# NHK2016mother.net
KiCad netlist of a schematic drawn in EAGLE
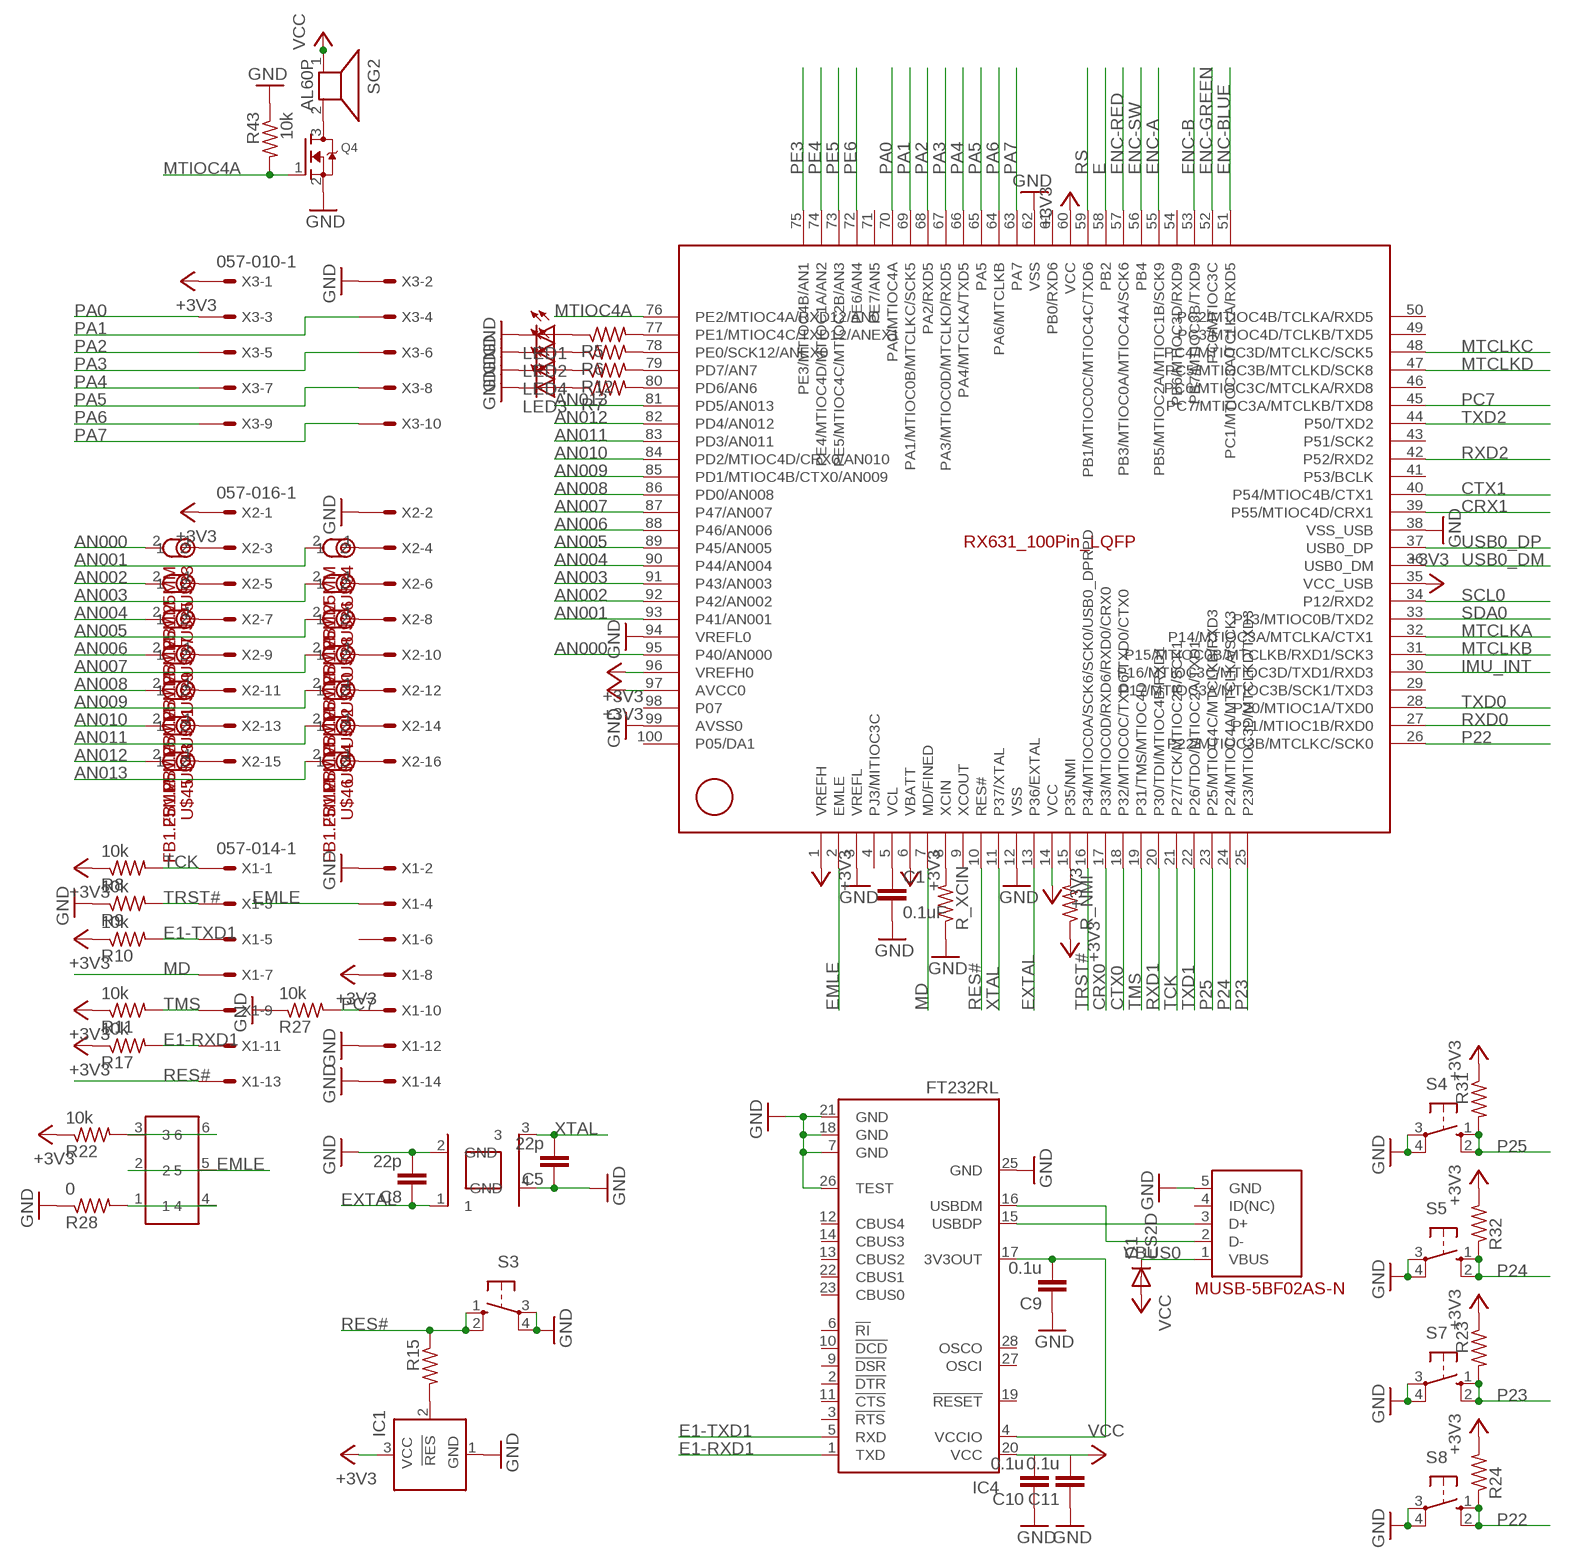
[diagram p0: schematic, sheet 1, part 1 of 2]
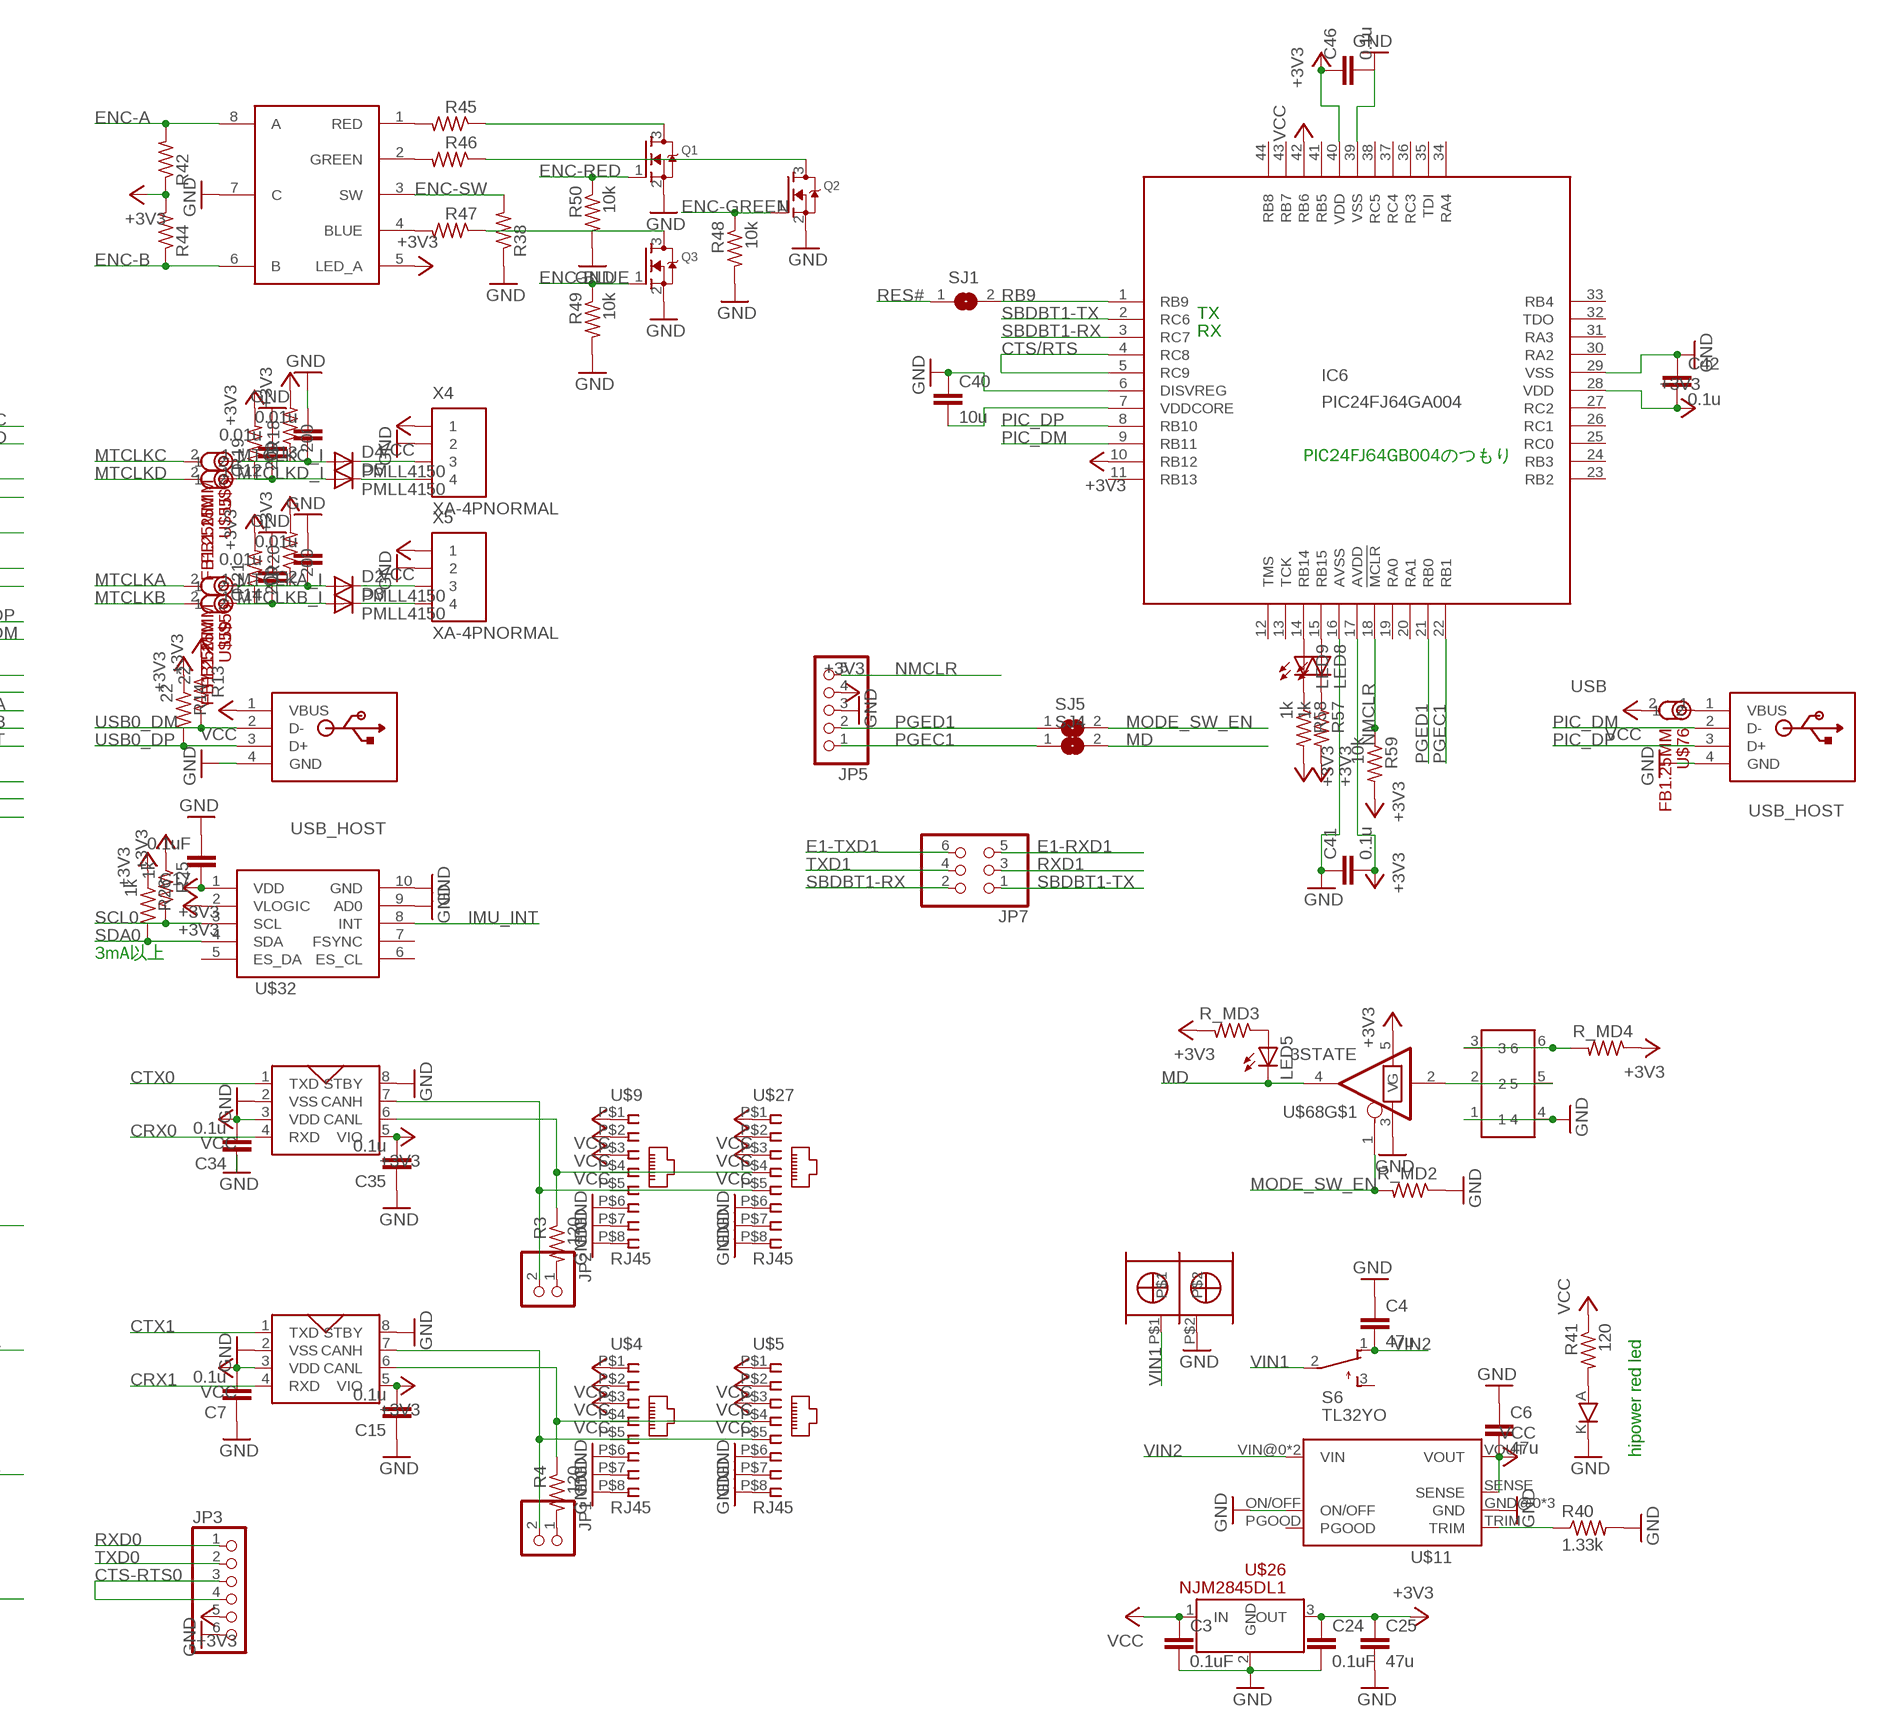
[diagram p1: schematic, sheet 1, part 2 of 2]

(export (version "E")
  (design (tool "Eeschema 10.0.6"))
  (components
    (comp (ref "C1")
      (value "0.1uF")
      (footprint "eagle-import:C0603K")
      (libsource (lib "eagle-import") (part "C-EUC0603K"))
    )
    (comp (ref "C2")
      (value "0.01u")
      (footprint "eagle-import:C0402")
      (libsource (lib "eagle-import") (part "C-EUC0402"))
    )
    (comp (ref "C3")
      (value "0.1uF")
      (footprint "eagle-import:C0603K")
      (libsource (lib "eagle-import") (part "C-EUC0603K"))
    )
    (comp (ref "C4")
      (value "47u")
      (footprint "eagle-import:C3225")
      (libsource (lib "eagle-import") (part "C-EUC3225"))
    )
    (comp (ref "C5")
      (value "22p")
      (footprint "eagle-import:C0603K")
      (libsource (lib "eagle-import") (part "C-EUC0603K"))
    )
    (comp (ref "C6")
      (value "47u")
      (footprint "eagle-import:C3225")
      (libsource (lib "eagle-import") (part "C-EUC3225"))
    )
    (comp (ref "C7")
      (value "0.1u")
      (footprint "eagle-import:C0402")
      (libsource (lib "eagle-import") (part "C-EUC0402"))
    )
    (comp (ref "C8")
      (value "22p")
      (footprint "eagle-import:C0603K")
      (libsource (lib "eagle-import") (part "C-EUC0603K"))
    )
    (comp (ref "C9")
      (value "0.1u")
      (footprint "eagle-import:C0402")
      (libsource (lib "eagle-import") (part "C-EUC0402"))
    )
    (comp (ref "C10")
      (value "0.1u")
      (footprint "eagle-import:C0402")
      (libsource (lib "eagle-import") (part "C-EUC0402"))
    )
    (comp (ref "C11")
      (value "0.1u")
      (footprint "eagle-import:C0402")
      (libsource (lib "eagle-import") (part "C-EUC0402"))
    )
    (comp (ref "C12")
      (value "0.01u")
      (footprint "eagle-import:C0402")
      (libsource (lib "eagle-import") (part "C-EUC0402"))
    )
    (comp (ref "C13")
      (value "0.01u")
      (footprint "eagle-import:C0402")
      (libsource (lib "eagle-import") (part "C-EUC0402"))
    )
    (comp (ref "C14")
      (value "0.01u")
      (footprint "eagle-import:C0402")
      (libsource (lib "eagle-import") (part "C-EUC0402"))
    )
    (comp (ref "C15")
      (value "0.1u")
      (footprint "eagle-import:C0402")
      (libsource (lib "eagle-import") (part "C-EUC0402"))
    )
    (comp (ref "C17")
      (value "0.1uF")
      (footprint "eagle-import:C0603K")
      (libsource (lib "eagle-import") (part "C-EUC0603K"))
    )
    (comp (ref "C24")
      (value "0.1uF")
      (footprint "eagle-import:C0603K")
      (libsource (lib "eagle-import") (part "C-EUC0603K"))
    )
    (comp (ref "C25")
      (value "47u")
      (footprint "eagle-import:C3225")
      (libsource (lib "eagle-import") (part "C-EUC3225"))
    )
    (comp (ref "C34")
      (value "0.1u")
      (footprint "eagle-import:C0402")
      (libsource (lib "eagle-import") (part "C-EUC0402"))
    )
    (comp (ref "C35")
      (value "0.1u")
      (footprint "eagle-import:C0402")
      (libsource (lib "eagle-import") (part "C-EUC0402"))
    )
    (comp (ref "C40")
      (value "10u")
      (footprint "eagle-import:C0603K")
      (libsource (lib "eagle-import") (part "C-EUC0603K"))
    )
    (comp (ref "C41")
      (value "0.1u")
      (footprint "eagle-import:C0603K")
      (libsource (lib "eagle-import") (part "C-EUC0603K"))
    )
    (comp (ref "C42")
      (value "0.1u")
      (footprint "eagle-import:C0603K")
      (libsource (lib "eagle-import") (part "C-EUC0603K"))
    )
    (comp (ref "C46")
      (value "0.1u")
      (footprint "eagle-import:C0603K")
      (libsource (lib "eagle-import") (part "C-EUC0603K"))
    )
    (comp (ref "D1")
      (value "ES2D")
      (footprint "eagle-import:SMB")
      (libsource (lib "eagle-import") (part "ES2D"))
    )
    (comp (ref "D2")
      (value "PMLL4150")
      (footprint "eagle-import:SOD80C")
      (libsource (lib "eagle-import") (part "PMLL4150"))
    )
    (comp (ref "D3")
      (value "PMLL4150")
      (footprint "eagle-import:SOD80C")
      (libsource (lib "eagle-import") (part "PMLL4150"))
    )
    (comp (ref "D4")
      (value "PMLL4150")
      (footprint "eagle-import:SOD80C")
      (libsource (lib "eagle-import") (part "PMLL4150"))
    )
    (comp (ref "D5")
      (value "PMLL4150")
      (footprint "eagle-import:SOD80C")
      (libsource (lib "eagle-import") (part "PMLL4150"))
    )
    (comp (ref "IC1")
      (value "TCM809")
      (footprint "eagle-import:SOT23B-3")
      (fields (field (name "MF") "MICROCHIP") (field (name "MPN") "TCM809MENB713"))
      (libsource (lib "eagle-import") (part "TCM809"))
    )
    (comp (ref "IC4")
      (value "FT232RL")
      (footprint "eagle-import:SSOP28")
      (libsource (lib "eagle-import") (part "FT232RL"))
    )
    (comp (ref "IC6")
      (value "PIC24FJ64GA004")
      (footprint "eagle-import:TQFP44")
      (fields (field (name "MPN") "PIC24FJ64GA004-E/PT"))
      (libsource (lib "eagle-import") (part "PIC24FJ64GA004"))
    )
    (comp (ref "JP1")
      (value "PINHD-1X2")
      (footprint "eagle-import:1X02")
      (libsource (lib "eagle-import") (part "PINHD-1X2"))
    )
    (comp (ref "JP2")
      (value "PINHD-1X2")
      (footprint "eagle-import:1X02")
      (libsource (lib "eagle-import") (part "PINHD-1X2"))
    )
    (comp (ref "JP3")
      (value "PINHD-1X6")
      (footprint "eagle-import:1X06")
      (libsource (lib "eagle-import") (part "PINHD-1X6"))
    )
    (comp (ref "JP5")
      (value "PINHD-1X5")
      (footprint "eagle-import:1X05")
      (libsource (lib "eagle-import") (part "PINHD-1X5"))
    )
    (comp (ref "JP7")
      (value "PINHD-2X3")
      (footprint "eagle-import:2X03")
      (libsource (lib "eagle-import") (part "PINHD-2X3"))
    )
    (comp (ref "LED1")
      (value "LEDSML0805")
      (footprint "eagle-import:SML0805")
      (libsource (lib "eagle-import") (part "LEDSML0805"))
    )
    (comp (ref "LED2")
      (value "LEDSML0805")
      (footprint "eagle-import:SML0805")
      (libsource (lib "eagle-import") (part "LEDSML0805"))
    )
    (comp (ref "LED3")
      (value "LEDSML0805")
      (footprint "eagle-import:SML0805")
      (libsource (lib "eagle-import") (part "LEDSML0805"))
    )
    (comp (ref "LED4")
      (value "LEDSML0805")
      (footprint "eagle-import:SML0805")
      (libsource (lib "eagle-import") (part "LEDSML0805"))
    )
    (comp (ref "LED5")
      (value "LEDSML0805")
      (footprint "eagle-import:SML0805")
      (libsource (lib "eagle-import") (part "LEDSML0805"))
    )
    (comp (ref "LED8")
      (value "LEDSML0805")
      (footprint "eagle-import:SML0805")
      (libsource (lib "eagle-import") (part "LEDSML0805"))
    )
    (comp (ref "LED9")
      (value "LEDSML0805")
      (footprint "eagle-import:SML0805")
      (libsource (lib "eagle-import") (part "LEDSML0805"))
    )
    (comp (ref "Q1")
      (value "MOSFET-NREFLOW")
      (footprint "eagle-import:SOT23")
      (libsource (lib "eagle-import") (part "MOSFET-NREFLOW"))
    )
    (comp (ref "Q2")
      (value "MOSFET-NREFLOW")
      (footprint "eagle-import:SOT23")
      (libsource (lib "eagle-import") (part "MOSFET-NREFLOW"))
    )
    (comp (ref "Q3")
      (value "MOSFET-NREFLOW")
      (footprint "eagle-import:SOT23")
      (libsource (lib "eagle-import") (part "MOSFET-NREFLOW"))
    )
    (comp (ref "Q4")
      (value "MOSFET-NREFLOW")
      (footprint "eagle-import:SOT23")
      (libsource (lib "eagle-import") (part "MOSFET-NREFLOW"))
    )
    (comp (ref "R3")
      (value "120")
      (footprint "eagle-import:MINI_MELF-0102W")
      (libsource (lib "eagle-import") (part "R-US_MELF0102W"))
    )
    (comp (ref "R4")
      (value "120")
      (footprint "eagle-import:MINI_MELF-0102W")
      (libsource (lib "eagle-import") (part "R-US_MELF0102W"))
    )
    (comp (ref "R5")
      (value "R-US_MELF0102W")
      (footprint "eagle-import:MINI_MELF-0102W")
      (libsource (lib "eagle-import") (part "R-US_MELF0102W"))
    )
    (comp (ref "R6")
      (value "R-US_MELF0102W")
      (footprint "eagle-import:MINI_MELF-0102W")
      (libsource (lib "eagle-import") (part "R-US_MELF0102W"))
    )
    (comp (ref "R7")
      (value "R-US_MELF0102W")
      (footprint "eagle-import:MINI_MELF-0102W")
      (libsource (lib "eagle-import") (part "R-US_MELF0102W"))
    )
    (comp (ref "R8")
      (value "10k")
      (footprint "eagle-import:MINI_MELF-0102W")
      (libsource (lib "eagle-import") (part "R-US_MELF0102W"))
    )
    (comp (ref "R9")
      (value "10k")
      (footprint "eagle-import:MINI_MELF-0102W")
      (libsource (lib "eagle-import") (part "R-US_MELF0102W"))
    )
    (comp (ref "R10")
      (value "10k")
      (footprint "eagle-import:MINI_MELF-0102W")
      (libsource (lib "eagle-import") (part "R-US_MELF0102W"))
    )
    (comp (ref "R11")
      (value "10k")
      (footprint "eagle-import:MINI_MELF-0102W")
      (libsource (lib "eagle-import") (part "R-US_MELF0102W"))
    )
    (comp (ref "R12")
      (value "R-US_MELF0102W")
      (footprint "eagle-import:MINI_MELF-0102W")
      (libsource (lib "eagle-import") (part "R-US_MELF0102W"))
    )
    (comp (ref "R13")
      (value "22")
      (footprint "eagle-import:MINI_MELF-0102W")
      (libsource (lib "eagle-import") (part "R-US_MELF0102W"))
    )
    (comp (ref "R14")
      (value "22")
      (footprint "eagle-import:MINI_MELF-0102W")
      (libsource (lib "eagle-import") (part "R-US_MELF0102W"))
    )
    (comp (ref "R15")
      (value "R-US_MELF0102W")
      (footprint "eagle-import:MINI_MELF-0102W")
      (libsource (lib "eagle-import") (part "R-US_MELF0102W"))
    )
    (comp (ref "R17")
      (value "10k")
      (footprint "eagle-import:MINI_MELF-0102W")
      (libsource (lib "eagle-import") (part "R-US_MELF0102W"))
    )
    (comp (ref "R18")
      (value "200")
      (footprint "eagle-import:MINI_MELF-0102W")
      (libsource (lib "eagle-import") (part "R-US_MELF0102W"))
    )
    (comp (ref "R19")
      (value "200")
      (footprint "eagle-import:MINI_MELF-0102W")
      (libsource (lib "eagle-import") (part "R-US_MELF0102W"))
    )
    (comp (ref "R20")
      (value "200")
      (footprint "eagle-import:MINI_MELF-0102W")
      (libsource (lib "eagle-import") (part "R-US_MELF0102W"))
    )
    (comp (ref "R21")
      (value "200")
      (footprint "eagle-import:MINI_MELF-0102W")
      (libsource (lib "eagle-import") (part "R-US_MELF0102W"))
    )
    (comp (ref "R22")
      (value "10k")
      (footprint "eagle-import:MINI_MELF-0102W")
      (libsource (lib "eagle-import") (part "R-US_MELF0102W"))
    )
    (comp (ref "R23")
      (value "R-US_MELF0102W")
      (footprint "eagle-import:MINI_MELF-0102W")
      (libsource (lib "eagle-import") (part "R-US_MELF0102W"))
    )
    (comp (ref "R24")
      (value "R-US_MELF0102W")
      (footprint "eagle-import:MINI_MELF-0102W")
      (libsource (lib "eagle-import") (part "R-US_MELF0102W"))
    )
    (comp (ref "R25")
      (value "1k")
      (footprint "eagle-import:MINI_MELF-0102W")
      (libsource (lib "eagle-import") (part "R-US_MELF0102W"))
    )
    (comp (ref "R26")
      (value "1k")
      (footprint "eagle-import:MINI_MELF-0102W")
      (libsource (lib "eagle-import") (part "R-US_MELF0102W"))
    )
    (comp (ref "R27")
      (value "10k")
      (footprint "eagle-import:MINI_MELF-0102W")
      (libsource (lib "eagle-import") (part "R-US_MELF0102W"))
    )
    (comp (ref "R28")
      (value "0")
      (footprint "eagle-import:MINI_MELF-0102W")
      (libsource (lib "eagle-import") (part "R-US_MELF0102W"))
    )
    (comp (ref "R31")
      (value "R-US_MELF0102W")
      (footprint "eagle-import:MINI_MELF-0102W")
      (libsource (lib "eagle-import") (part "R-US_MELF0102W"))
    )
    (comp (ref "R32")
      (value "R-US_MELF0102W")
      (footprint "eagle-import:MINI_MELF-0102W")
      (libsource (lib "eagle-import") (part "R-US_MELF0102W"))
    )
    (comp (ref "R38")
      (value "R-US_MELF0102W")
      (footprint "eagle-import:MINI_MELF-0102W")
      (libsource (lib "eagle-import") (part "R-US_MELF0102W"))
    )
    (comp (ref "R40")
      (value "1.33k")
      (footprint "eagle-import:MINI_MELF-0102W")
      (libsource (lib "eagle-import") (part "R-US_MELF0102W"))
    )
    (comp (ref "R41")
      (value "120")
      (footprint "eagle-import:MINI_MELF-0102W")
      (libsource (lib "eagle-import") (part "R-US_MELF0102W"))
    )
    (comp (ref "R42")
      (value "R-US_MELF0102W")
      (footprint "eagle-import:MINI_MELF-0102W")
      (libsource (lib "eagle-import") (part "R-US_MELF0102W"))
    )
    (comp (ref "R43")
      (value "10k")
      (footprint "eagle-import:MINI_MELF-0102W")
      (libsource (lib "eagle-import") (part "R-US_MELF0102W"))
    )
    (comp (ref "R44")
      (value "R-US_MELF0102W")
      (footprint "eagle-import:MINI_MELF-0102W")
      (libsource (lib "eagle-import") (part "R-US_MELF0102W"))
    )
    (comp (ref "R45")
      (value "R-US_MELF0102W")
      (footprint "eagle-import:MINI_MELF-0102W")
      (libsource (lib "eagle-import") (part "R-US_MELF0102W"))
    )
    (comp (ref "R46")
      (value "R-US_MELF0102W")
      (footprint "eagle-import:MINI_MELF-0102W")
      (libsource (lib "eagle-import") (part "R-US_MELF0102W"))
    )
    (comp (ref "R47")
      (value "R-US_MELF0102W")
      (footprint "eagle-import:MINI_MELF-0102W")
      (libsource (lib "eagle-import") (part "R-US_MELF0102W"))
    )
    (comp (ref "R48")
      (value "10k")
      (footprint "eagle-import:MINI_MELF-0102W")
      (libsource (lib "eagle-import") (part "R-US_MELF0102W"))
    )
    (comp (ref "R49")
      (value "10k")
      (footprint "eagle-import:MINI_MELF-0102W")
      (libsource (lib "eagle-import") (part "R-US_MELF0102W"))
    )
    (comp (ref "R50")
      (value "10k")
      (footprint "eagle-import:MINI_MELF-0102W")
      (libsource (lib "eagle-import") (part "R-US_MELF0102W"))
    )
    (comp (ref "R57")
      (value "1k")
      (footprint "eagle-import:MINI_MELF-0102W")
      (libsource (lib "eagle-import") (part "R-US_MELF0102W"))
    )
    (comp (ref "R58")
      (value "1k")
      (footprint "eagle-import:MINI_MELF-0102W")
      (libsource (lib "eagle-import") (part "R-US_MELF0102W"))
    )
    (comp (ref "R59")
      (value "10k")
      (footprint "eagle-import:MINI_MELF-0102W")
      (libsource (lib "eagle-import") (part "R-US_MELF0102W"))
    )
    (comp (ref "R_MD2")
      (value "R-US_MELF0102W")
      (footprint "eagle-import:MINI_MELF-0102W")
      (libsource (lib "eagle-import") (part "R-US_MELF0102W"))
    )
    (comp (ref "R_MD3")
      (value "R-US_MELF0102W")
      (footprint "eagle-import:MINI_MELF-0102W")
      (libsource (lib "eagle-import") (part "R-US_MELF0102W"))
    )
    (comp (ref "R_MD4")
      (value "R-US_MELF0102W")
      (footprint "eagle-import:MINI_MELF-0102W")
      (libsource (lib "eagle-import") (part "R-US_MELF0102W"))
    )
    (comp (ref "R_NMI")
      (value "R-US_MELF0102W")
      (footprint "eagle-import:MINI_MELF-0102W")
      (libsource (lib "eagle-import") (part "R-US_MELF0102W"))
    )
    (comp (ref "R_XCIN")
      (value "R-US_MELF0102W")
      (footprint "eagle-import:MINI_MELF-0102W")
      (libsource (lib "eagle-import") (part "R-US_MELF0102W"))
    )
    (comp (ref "S3")
      (value "10-XX")
      (footprint "eagle-import:B3F-10XX")
      (fields (field (name "MPN") "B3F-1000"))
      (libsource (lib "eagle-import") (part "10-XX"))
    )
    (comp (ref "S4")
      (value "10-XX")
      (footprint "eagle-import:B3F-10XX")
      (fields (field (name "MPN") "B3F-1000"))
      (libsource (lib "eagle-import") (part "10-XX"))
    )
    (comp (ref "S5")
      (value "10-XX")
      (footprint "eagle-import:B3F-10XX")
      (fields (field (name "MPN") "B3F-1000"))
      (libsource (lib "eagle-import") (part "10-XX"))
    )
    (comp (ref "S6")
      (value "TL32YO")
      (footprint "eagle-import:TL3XYO")
      (libsource (lib "eagle-import") (part "TL32YO"))
    )
    (comp (ref "S7")
      (value "10-XX")
      (footprint "eagle-import:B3F-10XX")
      (fields (field (name "MPN") "B3F-1000"))
      (libsource (lib "eagle-import") (part "10-XX"))
    )
    (comp (ref "S8")
      (value "10-XX")
      (footprint "eagle-import:B3F-10XX")
      (fields (field (name "MPN") "B3F-1000"))
      (libsource (lib "eagle-import") (part "10-XX"))
    )
    (comp (ref "SG2")
      (value "AL60P")
      (footprint "eagle-import:AL60P")
      (libsource (lib "eagle-import") (part "AL60P"))
    )
    (comp (ref "SJ1") (value "SJ") (footprint "eagle-import:SJ") (libsource (lib "eagle-import") (part "SJ")))
    (comp (ref "SJ4") (value "SJ") (footprint "eagle-import:SJ") (libsource (lib "eagle-import") (part "SJ")))
    (comp (ref "SJ5") (value "SJ") (footprint "eagle-import:SJ") (libsource (lib "eagle-import") (part "SJ")))
    (comp (ref "U$1")
      (value "R5F5631FDDFP")
      (footprint "eagle-import:LQFP100")
      (libsource (lib "eagle-import") (part "R5F5631FDDFP"))
    )
    (comp (ref "U$2")
      (value "MUSB-5BF02AS-N")
      (footprint "eagle-import:MUSB-5BF02AS-N")
      (libsource (lib "eagle-import") (part "MUSB-5BF02AS-N"))
    )
    (comp (ref "U$3")
      (value "MCP2562")
      (footprint "eagle-import:MCP2562")
      (libsource (lib "eagle-import") (part "MCP2562"))
    )
    (comp (ref "U$4")
      (value "RJ45")
      (footprint "eagle-import:RJ45")
      (libsource (lib "eagle-import") (part "RJ45"))
    )
    (comp (ref "U$5")
      (value "RJ45")
      (footprint "eagle-import:RJ45")
      (libsource (lib "eagle-import") (part "RJ45"))
    )
    (comp (ref "U$6")
      (value "FB1.25MM")
      (footprint "eagle-import:2012")
      (libsource (lib "eagle-import") (part "FB1.25MM"))
    )
    (comp (ref "U$7")
      (value "SSSS2")
      (footprint "eagle-import:SSSS2")
      (libsource (lib "eagle-import") (part "SSSS2"))
    )
    (comp (ref "U$8")
      (value "ＦＲ１１０５Ｗ－ＴＲ")
      (footprint "eagle-import:ＦＲ１１０５Ｗ－ＴＲ")
      (libsource (lib "eagle-import") (part "ＦＲ１１０５Ｗ－ＴＲ"))
    )
    (comp (ref "U$9")
      (value "RJ45")
      (footprint "eagle-import:RJ45")
      (libsource (lib "eagle-import") (part "RJ45"))
    )
    (comp (ref "U$10")
      (value "TERMINAL")
      (footprint "eagle-import:TERMINAL")
      (libsource (lib "eagle-import") (part "TERMINAL"))
    )
    (comp (ref "U$11")
      (value "OKL_T6_W12")
      (footprint "eagle-import:OKL_T6_W12")
      (libsource (lib "eagle-import") (part "OKL_T6_W12"))
    )
    (comp (ref "U$17")
      (value "MCP2562")
      (footprint "eagle-import:MCP2562")
      (libsource (lib "eagle-import") (part "MCP2562"))
    )
    (comp (ref "U$26")
      (value "NJM2845DL1")
      (footprint "eagle-import:TO-252-3-L1")
      (libsource (lib "eagle-import") (part "NJM2845DL1"))
    )
    (comp (ref "U$27")
      (value "RJ45")
      (footprint "eagle-import:RJ45")
      (libsource (lib "eagle-import") (part "RJ45"))
    )
    (comp (ref "U$29")
      (value "USB_A")
      (footprint "eagle-import:USB_A")
      (libsource (lib "eagle-import") (part "USB_A"))
    )
    (comp (ref "U$32")
      (value "MPU9150")
      (footprint "eagle-import:MPU9150")
      (libsource (lib "eagle-import") (part "MPU9150"))
    )
    (comp (ref "U$33")
      (value "FB1.25MM")
      (footprint "eagle-import:2012")
      (libsource (lib "eagle-import") (part "FB1.25MM"))
    )
    (comp (ref "U$34")
      (value "FB1.25MM")
      (footprint "eagle-import:2012")
      (libsource (lib "eagle-import") (part "FB1.25MM"))
    )
    (comp (ref "U$35")
      (value "FB1.25MM")
      (footprint "eagle-import:2012")
      (libsource (lib "eagle-import") (part "FB1.25MM"))
    )
    (comp (ref "U$36")
      (value "FB1.25MM")
      (footprint "eagle-import:2012")
      (libsource (lib "eagle-import") (part "FB1.25MM"))
    )
    (comp (ref "U$37")
      (value "FB1.25MM")
      (footprint "eagle-import:2012")
      (libsource (lib "eagle-import") (part "FB1.25MM"))
    )
    (comp (ref "U$38")
      (value "FB1.25MM")
      (footprint "eagle-import:2012")
      (libsource (lib "eagle-import") (part "FB1.25MM"))
    )
    (comp (ref "U$39")
      (value "FB1.25MM")
      (footprint "eagle-import:2012")
      (libsource (lib "eagle-import") (part "FB1.25MM"))
    )
    (comp (ref "U$40")
      (value "FB1.25MM")
      (footprint "eagle-import:2012")
      (libsource (lib "eagle-import") (part "FB1.25MM"))
    )
    (comp (ref "U$41")
      (value "FB1.25MM")
      (footprint "eagle-import:2012")
      (libsource (lib "eagle-import") (part "FB1.25MM"))
    )
    (comp (ref "U$42")
      (value "FB1.25MM")
      (footprint "eagle-import:2012")
      (libsource (lib "eagle-import") (part "FB1.25MM"))
    )
    (comp (ref "U$43")
      (value "FB1.25MM")
      (footprint "eagle-import:2012")
      (libsource (lib "eagle-import") (part "FB1.25MM"))
    )
    (comp (ref "U$44")
      (value "FB1.25MM")
      (footprint "eagle-import:2012")
      (libsource (lib "eagle-import") (part "FB1.25MM"))
    )
    (comp (ref "U$45")
      (value "FB1.25MM")
      (footprint "eagle-import:2012")
      (libsource (lib "eagle-import") (part "FB1.25MM"))
    )
    (comp (ref "U$46")
      (value "FB1.25MM")
      (footprint "eagle-import:2012")
      (libsource (lib "eagle-import") (part "FB1.25MM"))
    )
    (comp (ref "U$55")
      (value "FB1.25MM")
      (footprint "eagle-import:2012")
      (libsource (lib "eagle-import") (part "FB1.25MM"))
    )
    (comp (ref "U$56")
      (value "FB1.25MM")
      (footprint "eagle-import:2012")
      (libsource (lib "eagle-import") (part "FB1.25MM"))
    )
    (comp (ref "U$58")
      (value "EC12PLRGBSDVBF")
      (footprint "eagle-import:EC12PLRGBSDVBF")
      (libsource (lib "eagle-import") (part "EC12PLRGBSDVBF"))
    )
    (comp (ref "U$59")
      (value "FB1.25MM")
      (footprint "eagle-import:2012")
      (libsource (lib "eagle-import") (part "FB1.25MM"))
    )
    (comp (ref "U$61")
      (value "FA238V")
      (footprint "eagle-import:FA238V")
      (libsource (lib "eagle-import") (part "FA238V"))
    )
    (comp (ref "U$68")
      (value "3STATE")
      (footprint "eagle-import:SOT23-5")
      (libsource (lib "eagle-import") (part "3STATE"))
    )
    (comp (ref "U$75")
      (value "USB_A")
      (footprint "eagle-import:USB_A")
      (libsource (lib "eagle-import") (part "USB_A"))
    )
    (comp (ref "U$76")
      (value "FB1.25MM")
      (footprint "eagle-import:2012")
      (libsource (lib "eagle-import") (part "FB1.25MM"))
    )
    (comp (ref "U$82")
      (value "SSSS2")
      (footprint "eagle-import:SSSS2")
      (libsource (lib "eagle-import") (part "SSSS2"))
    )
    (comp (ref "X1")
      (value "057-014-1")
      (footprint "eagle-import:057-014-1")
      (libsource (lib "eagle-import") (part "057-014-1"))
    )
    (comp (ref "X2")
      (value "057-016-1")
      (footprint "eagle-import:057-016-1")
      (libsource (lib "eagle-import") (part "057-016-1"))
    )
    (comp (ref "X3")
      (value "057-010-1")
      (footprint "eagle-import:057-010-1")
      (libsource (lib "eagle-import") (part "057-010-1"))
    )
    (comp (ref "X4")
      (value "XA-4PNORMAL")
      (footprint "eagle-import:XA-4P")
      (libsource (lib "eagle-import") (part "XA-4PNORMAL"))
    )
    (comp (ref "X5")
      (value "XA-4PNORMAL")
      (footprint "eagle-import:XA-4P")
      (libsource (lib "eagle-import") (part "XA-4PNORMAL"))
    )
  )
  (nets
    (net (code "1") (name "+3V3") (class "Default")
      (node (ref "C15") (pin "2") (pinfunction "2_2") (pintype "passive"))
      (node (ref "C17") (pin "1") (pinfunction "1_1") (pintype "passive"))
      (node (ref "C24") (pin "1") (pinfunction "1_1") (pintype "passive"))
      (node (ref "C25") (pin "1") (pinfunction "1_1") (pintype "passive"))
      (node (ref "C35") (pin "2") (pinfunction "2_2") (pintype "passive"))
      (node (ref "C41") (pin "2") (pinfunction "2_2") (pintype "passive"))
      (node (ref "C42") (pin "2") (pinfunction "2_2") (pintype "passive"))
      (node (ref "C46") (pin "1") (pinfunction "1_1") (pintype "passive"))
      (node (ref "IC1") (pin "3") (pinfunction "VCC_3") (pintype "power_in"))
      (node (ref "IC6") (pin "10") (pinfunction "RB12_10") (pintype "bidirectional"))
      (node (ref "IC6") (pin "17") (pinfunction "AVDD_17") (pintype "power_in"))
      (node (ref "IC6") (pin "28") (pinfunction "VDD_28") (pintype "power_in"))
      (node (ref "IC6") (pin "40") (pinfunction "VDD_40") (pintype "power_in"))
      (node (ref "JP3") (pin "5") (pinfunction "5_5") (pintype "passive"))
      (node (ref "JP5") (pin "4") (pinfunction "4_4") (pintype "passive"))
      (node (ref "R10") (pin "1") (pinfunction "1_1") (pintype "passive"))
      (node (ref "R11") (pin "1") (pinfunction "1_1") (pintype "passive"))
      (node (ref "R13") (pin "1") (pinfunction "1_1") (pintype "passive"))
      (node (ref "R14") (pin "1") (pinfunction "1_1") (pintype "passive"))
      (node (ref "R17") (pin "1") (pinfunction "1_1") (pintype "passive"))
      (node (ref "R18") (pin "2") (pinfunction "2_2") (pintype "passive"))
      (node (ref "R19") (pin "2") (pinfunction "2_2") (pintype "passive"))
      (node (ref "R20") (pin "2") (pinfunction "2_2") (pintype "passive"))
      (node (ref "R21") (pin "2") (pinfunction "2_2") (pintype "passive"))
      (node (ref "R22") (pin "1") (pinfunction "1_1") (pintype "passive"))
      (node (ref "R23") (pin "1") (pinfunction "1_1") (pintype "passive"))
      (node (ref "R24") (pin "2") (pinfunction "2_2") (pintype "passive"))
      (node (ref "R25") (pin "1") (pinfunction "1_1") (pintype "passive"))
      (node (ref "R26") (pin "1") (pinfunction "1_1") (pintype "passive"))
      (node (ref "R31") (pin "1") (pinfunction "1_1") (pintype "passive"))
      (node (ref "R32") (pin "2") (pinfunction "2_2") (pintype "passive"))
      (node (ref "R42") (pin "1") (pinfunction "1_1") (pintype "passive"))
      (node (ref "R44") (pin "2") (pinfunction "2_2") (pintype "passive"))
      (node (ref "R57") (pin "2") (pinfunction "2_2") (pintype "passive"))
      (node (ref "R58") (pin "2") (pinfunction "2_2") (pintype "passive"))
      (node (ref "R59") (pin "2") (pinfunction "2_2") (pintype "passive"))
      (node (ref "R8") (pin "1") (pinfunction "1_1") (pintype "passive"))
      (node (ref "R_MD3") (pin "2") (pinfunction "2_2") (pintype "passive"))
      (node (ref "R_MD4") (pin "1") (pinfunction "1_1") (pintype "passive"))
      (node (ref "R_NMI") (pin "1") (pinfunction "1_1") (pintype "passive"))
      (node (ref "U$1") (pin "1") (pinfunction "VREFH_1") (pintype "bidirectional"))
      (node (ref "U$1") (pin "14") (pinfunction "VCC_14") (pintype "bidirectional"))
      (node (ref "U$1") (pin "35") (pinfunction "VCC_USB_35") (pintype "bidirectional"))
      (node (ref "U$1") (pin "6") (pinfunction "VBATT_6") (pintype "bidirectional"))
      (node (ref "U$1") (pin "60") (pinfunction "VCC_60") (pintype "bidirectional"))
      (node (ref "U$1") (pin "96") (pinfunction "VREFH0_96") (pintype "bidirectional"))
      (node (ref "U$1") (pin "97") (pinfunction "AVCC0_97") (pintype "bidirectional"))
      (node (ref "U$17") (pin "5") (pinfunction "VIO_5") (pintype "power_in"))
      (node (ref "U$26") (pin "3") (pinfunction "OUT_3") (pintype "power_in"))
      (node (ref "U$3") (pin "5") (pinfunction "VIO_5") (pintype "power_in"))
      (node (ref "U$32") (pin "1") (pinfunction "VDD_1") (pintype "bidirectional"))
      (node (ref "U$32") (pin "2") (pinfunction "VLOGIC_2") (pintype "bidirectional"))
      (node (ref "U$58") (pin "5") (pinfunction "LED_A_5") (pintype "bidirectional"))
      (node (ref "U$68") (pin "5") (pinfunction "V_5") (pintype "bidirectional"))
      (node (ref "X1") (pin "8") (pinfunction "S_8") (pintype "passive"))
      (node (ref "X2") (pin "1") (pinfunction "S_1") (pintype "passive"))
      (node (ref "X3") (pin "1") (pinfunction "S_1") (pintype "passive"))
    )
    (net (code "2") (name "/AN000") (class "Default")
      (node (ref "U$1") (pin "95") (pinfunction "P40/AN000_95") (pintype "bidirectional"))
      (node (ref "U$33") (pin "2") (pinfunction "2_2") (pintype "passive"))
    )
    (net (code "3") (name "/AN001") (class "Default")
      (node (ref "U$1") (pin "93") (pinfunction "P41/AN001_93") (pintype "bidirectional"))
      (node (ref "U$34") (pin "2") (pinfunction "2_2") (pintype "passive"))
    )
    (net (code "4") (name "/AN002") (class "Default")
      (node (ref "U$1") (pin "92") (pinfunction "P42/AN002_92") (pintype "bidirectional"))
      (node (ref "U$35") (pin "2") (pinfunction "2_2") (pintype "passive"))
    )
    (net (code "5") (name "/AN003") (class "Default")
      (node (ref "U$1") (pin "91") (pinfunction "P43/AN003_91") (pintype "bidirectional"))
      (node (ref "U$36") (pin "2") (pinfunction "2_2") (pintype "passive"))
    )
    (net (code "6") (name "/AN004") (class "Default")
      (node (ref "U$1") (pin "90") (pinfunction "P44/AN004_90") (pintype "bidirectional"))
      (node (ref "U$37") (pin "2") (pinfunction "2_2") (pintype "passive"))
    )
    (net (code "7") (name "/AN005") (class "Default")
      (node (ref "U$1") (pin "89") (pinfunction "P45/AN005_89") (pintype "bidirectional"))
      (node (ref "U$38") (pin "2") (pinfunction "2_2") (pintype "passive"))
    )
    (net (code "8") (name "/AN006") (class "Default")
      (node (ref "U$1") (pin "88") (pinfunction "P46/AN006_88") (pintype "bidirectional"))
      (node (ref "U$39") (pin "2") (pinfunction "2_2") (pintype "passive"))
    )
    (net (code "9") (name "/AN007") (class "Default")
      (node (ref "U$1") (pin "87") (pinfunction "P47/AN007_87") (pintype "bidirectional"))
      (node (ref "U$40") (pin "2") (pinfunction "2_2") (pintype "passive"))
    )
    (net (code "10") (name "/AN008") (class "Default")
      (node (ref "U$1") (pin "86") (pinfunction "PD0/AN008_86") (pintype "bidirectional"))
      (node (ref "U$41") (pin "2") (pinfunction "2_2") (pintype "passive"))
    )
    (net (code "11") (name "/AN009") (class "Default")
      (node (ref "U$1") (pin "85") (pinfunction "PD1/MTIOC4B/CTX0/AN009_85") (pintype "bidirectional"))
      (node (ref "U$42") (pin "2") (pinfunction "2_2") (pintype "passive"))
    )
    (net (code "12") (name "/AN010") (class "Default")
      (node (ref "U$1") (pin "84") (pinfunction "PD2/MTIOC4D/CRX0/AN010_84") (pintype "bidirectional"))
      (node (ref "U$43") (pin "2") (pinfunction "2_2") (pintype "passive"))
    )
    (net (code "13") (name "/AN011") (class "Default")
      (node (ref "U$1") (pin "83") (pinfunction "PD3/AN011_83") (pintype "bidirectional"))
      (node (ref "U$44") (pin "2") (pinfunction "2_2") (pintype "passive"))
    )
    (net (code "14") (name "/AN012") (class "Default")
      (node (ref "U$1") (pin "82") (pinfunction "PD4/AN012_82") (pintype "bidirectional"))
      (node (ref "U$45") (pin "2") (pinfunction "2_2") (pintype "passive"))
    )
    (net (code "15") (name "/AN013") (class "Default")
      (node (ref "U$1") (pin "81") (pinfunction "PD5/AN013_81") (pintype "bidirectional"))
      (node (ref "U$46") (pin "2") (pinfunction "2_2") (pintype "passive"))
    )
    (net (code "16") (name "/CRX0") (class "Default")
      (node (ref "U$1") (pin "17") (pinfunction "P33/MTIOC0D/RXD6/RXD0/CRX0_17") (pintype "bidirectional"))
      (node (ref "U$17") (pin "4") (pinfunction "RXD_4") (pintype "bidirectional"))
    )
    (net (code "17") (name "/CRX1") (class "Default")
      (node (ref "U$1") (pin "39") (pinfunction "P55/MTIOC4D/CRX1_39") (pintype "bidirectional"))
      (node (ref "U$3") (pin "4") (pinfunction "RXD_4") (pintype "bidirectional"))
    )
    (net (code "18") (name "/CTS-RTS0") (class "Default")
      (node (ref "JP3") (pin "3") (pinfunction "3_3") (pintype "passive"))
      (node (ref "JP3") (pin "4") (pinfunction "4_4") (pintype "passive"))
    )
    (net (code "19") (name "/CTS{slash}RTS") (class "Default")
      (node (ref "IC6") (pin "4") (pinfunction "RC8_4") (pintype "bidirectional"))
      (node (ref "IC6") (pin "5") (pinfunction "RC9_5") (pintype "bidirectional"))
    )
    (net (code "20") (name "/CTX0") (class "Default")
      (node (ref "U$1") (pin "18") (pinfunction "P32/MTIOC0C/TXD6/TXD0/CTX0_18") (pintype "bidirectional"))
      (node (ref "U$17") (pin "1") (pinfunction "TXD_1") (pintype "bidirectional"))
    )
    (net (code "21") (name "/CTX1") (class "Default")
      (node (ref "U$1") (pin "40") (pinfunction "P54/MTIOC4B/CTX1_40") (pintype "bidirectional"))
      (node (ref "U$3") (pin "1") (pinfunction "TXD_1") (pintype "bidirectional"))
    )
    (net (code "22") (name "/E") (class "Default")
      (node (ref "U$1") (pin "58") (pinfunction "PB2_58") (pintype "bidirectional"))
    )
    (net (code "23") (name "/E1-RXD1") (class "Default")
      (node (ref "IC4") (pin "1") (pinfunction "TXD_1") (pintype "output"))
      (node (ref "JP7") (pin "5") (pinfunction "5_5") (pintype "passive"))
      (node (ref "R17") (pin "2") (pinfunction "2_2") (pintype "passive"))
      (node (ref "X1") (pin "11") (pinfunction "S_11") (pintype "passive"))
    )
    (net (code "24") (name "/E1-TXD1") (class "Default")
      (node (ref "IC4") (pin "5") (pinfunction "RXD_5") (pintype "input"))
      (node (ref "JP7") (pin "6") (pinfunction "6_6") (pintype "passive"))
      (node (ref "R10") (pin "2") (pinfunction "2_2") (pintype "passive"))
      (node (ref "X1") (pin "5") (pinfunction "S_5") (pintype "passive"))
    )
    (net (code "25") (name "/EMLE") (class "Default")
      (node (ref "U$1") (pin "2") (pinfunction "EMLE_2") (pintype "bidirectional"))
      (node (ref "U$7") (pin "2") (pinfunction "2_2") (pintype "bidirectional"))
      (node (ref "U$7") (pin "5") (pinfunction "5_5") (pintype "bidirectional"))
      (node (ref "X1") (pin "4") (pinfunction "S_4") (pintype "passive"))
    )
    (net (code "26") (name "/ENC-A") (class "Default")
      (node (ref "R42") (pin "2") (pinfunction "2_2") (pintype "passive"))
      (node (ref "U$1") (pin "55") (pinfunction "PB5/MTIOC2A/MTIOC1B/SCK9_55") (pintype "bidirectional"))
      (node (ref "U$58") (pin "8") (pinfunction "A_8") (pintype "bidirectional"))
    )
    (net (code "27") (name "/ENC-B") (class "Default")
      (node (ref "R44") (pin "1") (pinfunction "1_1") (pintype "passive"))
      (node (ref "U$1") (pin "53") (pinfunction "PB7/MTIOC3B/TXD9_53") (pintype "bidirectional"))
      (node (ref "U$58") (pin "6") (pinfunction "B_6") (pintype "bidirectional"))
    )
    (net (code "28") (name "/ENC-BLUE") (class "Default")
      (node (ref "Q3") (pin "1") (pinfunction "G_1") (pintype "bidirectional"))
      (node (ref "R49") (pin "1") (pinfunction "1_1") (pintype "passive"))
      (node (ref "U$1") (pin "51") (pinfunction "PC1/MTIOC3A/TCLKA/RXD5_51") (pintype "bidirectional"))
    )
    (net (code "29") (name "/ENC-GREEN") (class "Default")
      (node (ref "Q2") (pin "1") (pinfunction "G_1") (pintype "bidirectional"))
      (node (ref "R48") (pin "1") (pinfunction "1_1") (pintype "passive"))
      (node (ref "U$1") (pin "52") (pinfunction "PC0/MTIOC3C_52") (pintype "bidirectional"))
    )
    (net (code "30") (name "/ENC-RED") (class "Default")
      (node (ref "Q1") (pin "1") (pinfunction "G_1") (pintype "bidirectional"))
      (node (ref "R50") (pin "1") (pinfunction "1_1") (pintype "passive"))
      (node (ref "U$1") (pin "57") (pinfunction "PB3/MTIOC0A/MTIOC4A/SCK6_57") (pintype "bidirectional"))
    )
    (net (code "31") (name "/ENC-SW") (class "Default")
      (node (ref "R38") (pin "2") (pinfunction "2_2") (pintype "passive"))
      (node (ref "U$1") (pin "56") (pinfunction "PB4_56") (pintype "bidirectional"))
      (node (ref "U$58") (pin "3") (pinfunction "SW_3") (pintype "bidirectional"))
    )
    (net (code "32") (name "/EXTAL") (class "Default")
      (node (ref "C8") (pin "1") (pinfunction "1_1") (pintype "passive"))
      (node (ref "U$1") (pin "13") (pinfunction "P36/EXTAL_13") (pintype "bidirectional"))
      (node (ref "U$61") (pin "1") (pinfunction "1_1") (pintype "bidirectional"))
    )
    (net (code "33") (name "/IMU_INT") (class "Default")
      (node (ref "U$1") (pin "30") (pinfunction "P16/MTIOC3C/MTIOC3D/TXD1/RXD3_30") (pintype "bidirectional"))
      (node (ref "U$32") (pin "8") (pinfunction "INT_8") (pintype "bidirectional"))
    )
    (net (code "34") (name "/MD") (class "Default")
      (node (ref "LED5") (pin "C") (pinfunction "C_C") (pintype "passive"))
      (node (ref "SJ4") (pin "2") (pinfunction "2_2") (pintype "passive"))
      (node (ref "U$1") (pin "7") (pinfunction "MD/FINED_7") (pintype "bidirectional"))
      (node (ref "U$68") (pin "4") (pinfunction "O_4") (pintype "tri_state"))
      (node (ref "X1") (pin "7") (pinfunction "S_7") (pintype "passive"))
    )
    (net (code "35") (name "/MODE_SW_EN") (class "Default")
      (node (ref "R_MD2") (pin "2") (pinfunction "2_2") (pintype "passive"))
      (node (ref "SJ5") (pin "2") (pinfunction "2_2") (pintype "passive"))
      (node (ref "U$68") (pin "1") (pinfunction "OE_1") (pintype "input"))
    )
    (net (code "36") (name "/MTCLKA") (class "Default")
      (node (ref "U$1") (pin "32") (pinfunction "P14/MTIOC3A/MTCLKA/CTX1_32") (pintype "bidirectional"))
      (node (ref "U$56") (pin "2") (pinfunction "2_2") (pintype "passive"))
    )
    (net (code "37") (name "/MTCLKA_I") (class "Default")
      (node (ref "C2") (pin "1") (pinfunction "1_1") (pintype "passive"))
      (node (ref "D2") (pin "A") (pinfunction "A_A") (pintype "passive"))
      (node (ref "R20") (pin "1") (pinfunction "1_1") (pintype "passive"))
      (node (ref "U$56") (pin "1") (pinfunction "1_1") (pintype "passive"))
    )
    (net (code "38") (name "/MTCLKB") (class "Default")
      (node (ref "U$1") (pin "31") (pinfunction "P15/MTIOC0B/MTCLKB/RXD1/SCK3_31") (pintype "bidirectional"))
      (node (ref "U$59") (pin "2") (pinfunction "2_2") (pintype "passive"))
    )
    (net (code "39") (name "/MTCLKB_I") (class "Default")
      (node (ref "C14") (pin "1") (pinfunction "1_1") (pintype "passive"))
      (node (ref "D3") (pin "A") (pinfunction "A_A") (pintype "passive"))
      (node (ref "R21") (pin "1") (pinfunction "1_1") (pintype "passive"))
      (node (ref "U$59") (pin "1") (pinfunction "1_1") (pintype "passive"))
    )
    (net (code "40") (name "/MTCLKC") (class "Default")
      (node (ref "U$1") (pin "48") (pinfunction "PC4/MTIOC3D/MTCLKC/SCK5_48") (pintype "bidirectional"))
      (node (ref "U$6") (pin "2") (pinfunction "2_2") (pintype "passive"))
    )
    (net (code "41") (name "/MTCLKC_I") (class "Default")
      (node (ref "C13") (pin "1") (pinfunction "1_1") (pintype "passive"))
      (node (ref "D4") (pin "A") (pinfunction "A_A") (pintype "passive"))
      (node (ref "R18") (pin "1") (pinfunction "1_1") (pintype "passive"))
      (node (ref "U$6") (pin "1") (pinfunction "1_1") (pintype "passive"))
    )
    (net (code "42") (name "/MTCLKD") (class "Default")
      (node (ref "U$1") (pin "47") (pinfunction "PC5/MTIOC3B/MTCLKD/SCK8_47") (pintype "bidirectional"))
      (node (ref "U$55") (pin "2") (pinfunction "2_2") (pintype "passive"))
    )
    (net (code "43") (name "/MTCLKD_I") (class "Default")
      (node (ref "C12") (pin "1") (pinfunction "1_1") (pintype "passive"))
      (node (ref "D5") (pin "A") (pinfunction "A_A") (pintype "passive"))
      (node (ref "R19") (pin "1") (pinfunction "1_1") (pintype "passive"))
      (node (ref "U$55") (pin "1") (pinfunction "1_1") (pintype "passive"))
    )
    (net (code "44") (name "/MTIOC4A") (class "Default")
      (node (ref "Q4") (pin "1") (pinfunction "G_1") (pintype "bidirectional"))
      (node (ref "R43") (pin "2") (pinfunction "2_2") (pintype "passive"))
      (node (ref "U$1") (pin "76") (pinfunction "PE2/MTIOC4A/RXD12/AN0_76") (pintype "bidirectional"))
    )
    (net (code "45") (name "/NMCLR") (class "Default")
      (node (ref "IC6") (pin "18") (pinfunction "~{MCLR}_18") (pintype "bidirectional"))
      (node (ref "JP5") (pin "5") (pinfunction "5_5") (pintype "passive"))
      (node (ref "R59") (pin "1") (pinfunction "1_1") (pintype "passive"))
    )
    (net (code "46") (name "/P22") (class "Default")
      (node (ref "R24") (pin "1") (pinfunction "1_1") (pintype "passive"))
      (node (ref "S8") (pin "1") (pinfunction "S_1") (pintype "passive"))
      (node (ref "S8") (pin "2") (pinfunction "S1_2") (pintype "passive"))
      (node (ref "U$1") (pin "26") (pinfunction "P22/MTIOC3B/MTCLKC/SCK0_26") (pintype "bidirectional"))
    )
    (net (code "47") (name "/P23") (class "Default")
      (node (ref "R23") (pin "2") (pinfunction "2_2") (pintype "passive"))
      (node (ref "S7") (pin "1") (pinfunction "S_1") (pintype "passive"))
      (node (ref "S7") (pin "2") (pinfunction "S1_2") (pintype "passive"))
      (node (ref "U$1") (pin "25") (pinfunction "P23/MTIOC3D/MTCLKD/TXD3_25") (pintype "bidirectional"))
    )
    (net (code "48") (name "/P24") (class "Default")
      (node (ref "R32") (pin "1") (pinfunction "1_1") (pintype "passive"))
      (node (ref "S5") (pin "1") (pinfunction "S_1") (pintype "passive"))
      (node (ref "S5") (pin "2") (pinfunction "S1_2") (pintype "passive"))
      (node (ref "U$1") (pin "24") (pinfunction "P24/MTIOC4A/MTCLKA/SCK3_24") (pintype "bidirectional"))
    )
    (net (code "49") (name "/P25") (class "Default")
      (node (ref "R31") (pin "2") (pinfunction "2_2") (pintype "passive"))
      (node (ref "S4") (pin "1") (pinfunction "S_1") (pintype "passive"))
      (node (ref "S4") (pin "2") (pinfunction "S1_2") (pintype "passive"))
      (node (ref "U$1") (pin "23") (pinfunction "P25/MTIOC4C/MTCLKB/RXD3_23") (pintype "bidirectional"))
    )
    (net (code "50") (name "/PA0") (class "Default")
      (node (ref "U$1") (pin "70") (pinfunction "PA0/MTIOC4A_70") (pintype "bidirectional"))
      (node (ref "X3") (pin "3") (pinfunction "S_3") (pintype "passive"))
    )
    (net (code "51") (name "/PA1") (class "Default")
      (node (ref "U$1") (pin "69") (pinfunction "PA1/MTIOC0B/MTCLKC/SCK5_69") (pintype "bidirectional"))
      (node (ref "X3") (pin "4") (pinfunction "S_4") (pintype "passive"))
    )
    (net (code "52") (name "/PA2") (class "Default")
      (node (ref "U$1") (pin "68") (pinfunction "PA2/RXD5_68") (pintype "bidirectional"))
      (node (ref "X3") (pin "5") (pinfunction "S_5") (pintype "passive"))
    )
    (net (code "53") (name "/PA3") (class "Default")
      (node (ref "U$1") (pin "67") (pinfunction "PA3/MTIOC0D/MTCLKD/RXD5_67") (pintype "bidirectional"))
      (node (ref "X3") (pin "6") (pinfunction "S_6") (pintype "passive"))
    )
    (net (code "54") (name "/PA4") (class "Default")
      (node (ref "U$1") (pin "66") (pinfunction "PA4/MTCLKA/TXD5_66") (pintype "bidirectional"))
      (node (ref "X3") (pin "7") (pinfunction "S_7") (pintype "passive"))
    )
    (net (code "55") (name "/PA5") (class "Default")
      (node (ref "U$1") (pin "65") (pinfunction "PA5_65") (pintype "bidirectional"))
      (node (ref "X3") (pin "8") (pinfunction "S_8") (pintype "passive"))
    )
    (net (code "56") (name "/PA6") (class "Default")
      (node (ref "U$1") (pin "64") (pinfunction "PA6/MTCLKB_64") (pintype "bidirectional"))
      (node (ref "X3") (pin "9") (pinfunction "S_9") (pintype "passive"))
    )
    (net (code "57") (name "/PA7") (class "Default")
      (node (ref "U$1") (pin "63") (pinfunction "PA7_63") (pintype "bidirectional"))
      (node (ref "X3") (pin "10") (pinfunction "S_10") (pintype "passive"))
    )
    (net (code "58") (name "/PC7") (class "Default")
      (node (ref "R27") (pin "2") (pinfunction "2_2") (pintype "passive"))
      (node (ref "U$1") (pin "45") (pinfunction "PC7/MTIOC3A/MTCLKB/TXD8_45") (pintype "bidirectional"))
      (node (ref "X1") (pin "10") (pinfunction "S_10") (pintype "passive"))
    )
    (net (code "59") (name "/PE3") (class "Default")
      (node (ref "U$1") (pin "75") (pinfunction "PE3/MTIOC4B/AN1_75") (pintype "bidirectional"))
    )
    (net (code "60") (name "/PE4") (class "Default")
      (node (ref "U$1") (pin "74") (pinfunction "PE4/MTIOC4D/MTIOC1A/AN2_74") (pintype "bidirectional"))
    )
    (net (code "61") (name "/PE5") (class "Default")
      (node (ref "U$1") (pin "73") (pinfunction "PE5/MTIOC4C/MTIOC2B/AN3_73") (pintype "bidirectional"))
    )
    (net (code "62") (name "/PE6") (class "Default")
      (node (ref "U$1") (pin "72") (pinfunction "PE6/AN4_72") (pintype "bidirectional"))
    )
    (net (code "63") (name "/PGEC1") (class "Default")
      (node (ref "IC6") (pin "22") (pinfunction "RB1_22") (pintype "bidirectional"))
      (node (ref "JP5") (pin "1") (pinfunction "1_1") (pintype "passive"))
      (node (ref "SJ4") (pin "1") (pinfunction "1_1") (pintype "passive"))
    )
    (net (code "64") (name "/PGED1") (class "Default")
      (node (ref "IC6") (pin "21") (pinfunction "RB0_21") (pintype "bidirectional"))
      (node (ref "JP5") (pin "2") (pinfunction "2_2") (pintype "passive"))
      (node (ref "SJ5") (pin "1") (pinfunction "1_1") (pintype "passive"))
    )
    (net (code "65") (name "/PIC_DM") (class "Default")
      (node (ref "IC6") (pin "9") (pinfunction "RB11_9") (pintype "bidirectional"))
      (node (ref "U$75") (pin "2") (pinfunction "D-_2") (pintype "bidirectional"))
    )
    (net (code "66") (name "/PIC_DP") (class "Default")
      (node (ref "IC6") (pin "8") (pinfunction "RB10_8") (pintype "bidirectional"))
      (node (ref "U$75") (pin "3") (pinfunction "D+_3") (pintype "bidirectional"))
    )
    (net (code "67") (name "/RB9") (class "Default")
      (node (ref "IC6") (pin "1") (pinfunction "RB9_1") (pintype "bidirectional"))
      (node (ref "SJ1") (pin "2") (pinfunction "2_2") (pintype "passive"))
    )
    (net (code "68") (name "/RES#") (class "Default")
      (node (ref "R15") (pin "1") (pinfunction "1_1") (pintype "passive"))
      (node (ref "S3") (pin "1") (pinfunction "S_1") (pintype "passive"))
      (node (ref "S3") (pin "2") (pinfunction "S1_2") (pintype "passive"))
      (node (ref "SJ1") (pin "1") (pinfunction "1_1") (pintype "passive"))
      (node (ref "U$1") (pin "10") (pinfunction "RES#_10") (pintype "bidirectional"))
      (node (ref "X1") (pin "13") (pinfunction "S_13") (pintype "passive"))
    )
    (net (code "69") (name "/RS") (class "Default")
      (node (ref "U$1") (pin "59") (pinfunction "PB1/MTIOC0C/MTIOC4C/TXD6_59") (pintype "bidirectional"))
    )
    (net (code "70") (name "/RXD0") (class "Default")
      (node (ref "JP3") (pin "1") (pinfunction "1_1") (pintype "passive"))
      (node (ref "U$1") (pin "27") (pinfunction "P21/MTIOC1B/RXD0_27") (pintype "bidirectional"))
    )
    (net (code "71") (name "/RXD1") (class "Default")
      (node (ref "JP7") (pin "3") (pinfunction "3_3") (pintype "passive"))
      (node (ref "U$1") (pin "20") (pinfunction "P30/TDI/MTIOC4B/RXD1_20") (pintype "bidirectional"))
    )
    (net (code "72") (name "/RXD2") (class "Default")
      (node (ref "U$1") (pin "42") (pinfunction "P52/RXD2_42") (pintype "bidirectional"))
    )
    (net (code "73") (name "/SBDBT1-RX") (class "Default")
      (node (ref "IC6") (pin "3") (pinfunction "RC7_3") (pintype "bidirectional"))
      (node (ref "JP7") (pin "2") (pinfunction "2_2") (pintype "passive"))
    )
    (net (code "74") (name "/SBDBT1-TX") (class "Default")
      (node (ref "IC6") (pin "2") (pinfunction "RC6_2") (pintype "bidirectional"))
      (node (ref "JP7") (pin "1") (pinfunction "1_1") (pintype "passive"))
    )
    (net (code "75") (name "/SCL0") (class "Default")
      (node (ref "R25") (pin "2") (pinfunction "2_2") (pintype "passive"))
      (node (ref "U$1") (pin "34") (pinfunction "P12/RXD2_34") (pintype "bidirectional"))
      (node (ref "U$32") (pin "3") (pinfunction "SCL_3") (pintype "bidirectional"))
    )
    (net (code "76") (name "/SDA0") (class "Default")
      (node (ref "R26") (pin "2") (pinfunction "2_2") (pintype "passive"))
      (node (ref "U$1") (pin "33") (pinfunction "P13/MTIOC0B/TXD2_33") (pintype "bidirectional"))
      (node (ref "U$32") (pin "4") (pinfunction "SDA_4") (pintype "bidirectional"))
    )
    (net (code "77") (name "/TCK") (class "Default")
      (node (ref "R8") (pin "2") (pinfunction "2_2") (pintype "passive"))
      (node (ref "U$1") (pin "21") (pinfunction "P27/TCK/MTIOC2B/SCK1_21") (pintype "bidirectional"))
      (node (ref "X1") (pin "1") (pinfunction "S_1") (pintype "passive"))
    )
    (net (code "78") (name "/TMS") (class "Default")
      (node (ref "R11") (pin "2") (pinfunction "2_2") (pintype "passive"))
      (node (ref "U$1") (pin "19") (pinfunction "P31/TMS/MTIOC4D_19") (pintype "bidirectional"))
      (node (ref "X1") (pin "9") (pinfunction "S_9") (pintype "passive"))
    )
    (net (code "79") (name "/TRST#") (class "Default")
      (node (ref "R9") (pin "2") (pinfunction "2_2") (pintype "passive"))
      (node (ref "U$1") (pin "16") (pinfunction "P34/MTIOC0A/SCK6/SCK0/USB0_DPRPD_16") (pintype "bidirectional"))
      (node (ref "X1") (pin "3") (pinfunction "S_3") (pintype "passive"))
    )
    (net (code "80") (name "/TXD0") (class "Default")
      (node (ref "JP3") (pin "2") (pinfunction "2_2") (pintype "passive"))
      (node (ref "U$1") (pin "28") (pinfunction "P20/MTIOC1A/TXD0_28") (pintype "bidirectional"))
    )
    (net (code "81") (name "/TXD1") (class "Default")
      (node (ref "JP7") (pin "4") (pinfunction "4_4") (pintype "passive"))
      (node (ref "U$1") (pin "22") (pinfunction "P26/TDO/MTIOC2A/TXD1_22") (pintype "bidirectional"))
    )
    (net (code "82") (name "/TXD2") (class "Default")
      (node (ref "U$1") (pin "44") (pinfunction "P50/TXD2_44") (pintype "bidirectional"))
    )
    (net (code "83") (name "/USB0_DM") (class "Default")
      (node (ref "R13") (pin "2") (pinfunction "2_2") (pintype "passive"))
      (node (ref "U$1") (pin "36") (pinfunction "USB0_DM_36") (pintype "bidirectional"))
      (node (ref "U$29") (pin "2") (pinfunction "D-_2") (pintype "bidirectional"))
    )
    (net (code "84") (name "/USB0_DP") (class "Default")
      (node (ref "R14") (pin "2") (pinfunction "2_2") (pintype "passive"))
      (node (ref "U$1") (pin "37") (pinfunction "USB0_DP_37") (pintype "bidirectional"))
      (node (ref "U$29") (pin "3") (pinfunction "D+_3") (pintype "bidirectional"))
    )
    (net (code "85") (name "/VBUS0") (class "Default")
      (node (ref "D1") (pin "C") (pinfunction "C_C") (pintype "passive"))
      (node (ref "U$2") (pin "1") (pinfunction "VBUS_1") (pintype "bidirectional"))
    )
    (net (code "86") (name "/VIN1") (class "Default")
      (node (ref "S6") (pin "2") (pinfunction "P_2") (pintype "passive"))
      (node (ref "U$10") (pin "P$1") (pinfunction "P$1_P$1") (pintype "bidirectional"))
    )
    (net (code "87") (name "/VIN2") (class "Default")
      (node (ref "C4") (pin "2") (pinfunction "2_2") (pintype "passive"))
      (node (ref "S6") (pin "1") (pinfunction "O_1") (pintype "passive"))
      (node (ref "U$11") (pin "VIN@0") (pinfunction "VIN_VIN@0") (pintype "bidirectional"))
      (node (ref "U$11") (pin "VIN@1") (pinfunction "VIN_VIN@1") (pintype "bidirectional"))
    )
    (net (code "88") (name "/XTAL") (class "Default")
      (node (ref "C5") (pin "2") (pinfunction "2_2") (pintype "passive"))
      (node (ref "U$1") (pin "11") (pinfunction "P37/XTAL_11") (pintype "bidirectional"))
      (node (ref "U$61") (pin "3") (pinfunction "3_3") (pintype "bidirectional"))
    )
    (net (code "89") (name "GND") (class "Default")
      (node (ref "C1") (pin "2") (pinfunction "2_2") (pintype "passive"))
      (node (ref "C10") (pin "1") (pinfunction "1_1") (pintype "passive"))
      (node (ref "C11") (pin "1") (pinfunction "1_1") (pintype "passive"))
      (node (ref "C12") (pin "2") (pinfunction "2_2") (pintype "passive"))
      (node (ref "C13") (pin "2") (pinfunction "2_2") (pintype "passive"))
      (node (ref "C14") (pin "2") (pinfunction "2_2") (pintype "passive"))
      (node (ref "C15") (pin "1") (pinfunction "1_1") (pintype "passive"))
      (node (ref "C17") (pin "2") (pinfunction "2_2") (pintype "passive"))
      (node (ref "C2") (pin "2") (pinfunction "2_2") (pintype "passive"))
      (node (ref "C24") (pin "2") (pinfunction "2_2") (pintype "passive"))
      (node (ref "C25") (pin "2") (pinfunction "2_2") (pintype "passive"))
      (node (ref "C3") (pin "2") (pinfunction "2_2") (pintype "passive"))
      (node (ref "C34") (pin "1") (pinfunction "1_1") (pintype "passive"))
      (node (ref "C35") (pin "1") (pinfunction "1_1") (pintype "passive"))
      (node (ref "C4") (pin "1") (pinfunction "1_1") (pintype "passive"))
      (node (ref "C40") (pin "1") (pinfunction "1_1") (pintype "passive"))
      (node (ref "C41") (pin "1") (pinfunction "1_1") (pintype "passive"))
      (node (ref "C42") (pin "1") (pinfunction "1_1") (pintype "passive"))
      (node (ref "C46") (pin "2") (pinfunction "2_2") (pintype "passive"))
      (node (ref "C5") (pin "1") (pinfunction "1_1") (pintype "passive"))
      (node (ref "C6") (pin "1") (pinfunction "1_1") (pintype "passive"))
      (node (ref "C7") (pin "1") (pinfunction "1_1") (pintype "passive"))
      (node (ref "C8") (pin "2") (pinfunction "2_2") (pintype "passive"))
      (node (ref "C9") (pin "1") (pinfunction "1_1") (pintype "passive"))
      (node (ref "IC1") (pin "1") (pinfunction "GND_1") (pintype "power_in"))
      (node (ref "IC4") (pin "18") (pinfunction "GND_18") (pintype "power_in"))
      (node (ref "IC4") (pin "21") (pinfunction "GND_21") (pintype "power_in"))
      (node (ref "IC4") (pin "25") (pinfunction "GND_25") (pintype "power_in"))
      (node (ref "IC4") (pin "26") (pinfunction "TEST_26") (pintype "input"))
      (node (ref "IC4") (pin "7") (pinfunction "GND_7") (pintype "power_in"))
      (node (ref "IC6") (pin "16") (pinfunction "AVSS_16") (pintype "power_in"))
      (node (ref "IC6") (pin "29") (pinfunction "VSS_29") (pintype "power_in"))
      (node (ref "IC6") (pin "39") (pinfunction "VSS_39") (pintype "power_in"))
      (node (ref "IC6") (pin "6") (pinfunction "DISVREG_6") (pintype "passive"))
      (node (ref "JP3") (pin "6") (pinfunction "6_6") (pintype "passive"))
      (node (ref "JP5") (pin "3") (pinfunction "3_3") (pintype "passive"))
      (node (ref "LED1") (pin "C") (pinfunction "C_C") (pintype "passive"))
      (node (ref "LED2") (pin "C") (pinfunction "C_C") (pintype "passive"))
      (node (ref "LED3") (pin "C") (pinfunction "C_C") (pintype "passive"))
      (node (ref "LED4") (pin "C") (pinfunction "C_C") (pintype "passive"))
      (node (ref "Q1") (pin "2") (pinfunction "S_2") (pintype "bidirectional"))
      (node (ref "Q2") (pin "2") (pinfunction "S_2") (pintype "bidirectional"))
      (node (ref "Q3") (pin "2") (pinfunction "S_2") (pintype "bidirectional"))
      (node (ref "Q4") (pin "2") (pinfunction "S_2") (pintype "bidirectional"))
      (node (ref "R27") (pin "1") (pinfunction "1_1") (pintype "passive"))
      (node (ref "R28") (pin "1") (pinfunction "1_1") (pintype "passive"))
      (node (ref "R38") (pin "1") (pinfunction "1_1") (pintype "passive"))
      (node (ref "R40") (pin "2") (pinfunction "2_2") (pintype "passive"))
      (node (ref "R43") (pin "1") (pinfunction "1_1") (pintype "passive"))
      (node (ref "R48") (pin "2") (pinfunction "2_2") (pintype "passive"))
      (node (ref "R49") (pin "2") (pinfunction "2_2") (pintype "passive"))
      (node (ref "R50") (pin "2") (pinfunction "2_2") (pintype "passive"))
      (node (ref "R9") (pin "1") (pinfunction "1_1") (pintype "passive"))
      (node (ref "R_MD2") (pin "1") (pinfunction "1_1") (pintype "passive"))
      (node (ref "R_XCIN") (pin "1") (pinfunction "1_1") (pintype "passive"))
      (node (ref "S3") (pin "3") (pinfunction "P_3") (pintype "passive"))
      (node (ref "S3") (pin "4") (pinfunction "P1_4") (pintype "passive"))
      (node (ref "S4") (pin "3") (pinfunction "P_3") (pintype "passive"))
      (node (ref "S4") (pin "4") (pinfunction "P1_4") (pintype "passive"))
      (node (ref "S5") (pin "3") (pinfunction "P_3") (pintype "passive"))
      (node (ref "S5") (pin "4") (pinfunction "P1_4") (pintype "passive"))
      (node (ref "S7") (pin "3") (pinfunction "P_3") (pintype "passive"))
      (node (ref "S7") (pin "4") (pinfunction "P1_4") (pintype "passive"))
      (node (ref "S8") (pin "3") (pinfunction "P_3") (pintype "passive"))
      (node (ref "S8") (pin "4") (pinfunction "P1_4") (pintype "passive"))
      (node (ref "U$1") (pin "12") (pinfunction "VSS_12") (pintype "bidirectional"))
      (node (ref "U$1") (pin "3") (pinfunction "VREFL_3") (pintype "bidirectional"))
      (node (ref "U$1") (pin "38") (pinfunction "VSS_USB_38") (pintype "bidirectional"))
      (node (ref "U$1") (pin "62") (pinfunction "VSS_62") (pintype "bidirectional"))
      (node (ref "U$1") (pin "94") (pinfunction "VREFL0_94") (pintype "bidirectional"))
      (node (ref "U$1") (pin "99") (pinfunction "AVSS0_99") (pintype "bidirectional"))
      (node (ref "U$10") (pin "P$2") (pinfunction "P$2_P$2") (pintype "bidirectional"))
      (node (ref "U$11") (pin "GND@0") (pinfunction "GND_GND@0") (pintype "bidirectional"))
      (node (ref "U$11") (pin "GND@1") (pinfunction "GND_GND@1") (pintype "bidirectional"))
      (node (ref "U$11") (pin "GND@2") (pinfunction "GND_GND@2") (pintype "bidirectional"))
      (node (ref "U$11") (pin "ON/OFF") (pinfunction "ON/OFF_ON/OFF") (pintype "bidirectional"))
      (node (ref "U$17") (pin "2") (pinfunction "VSS_2") (pintype "power_in"))
      (node (ref "U$17") (pin "8") (pinfunction "STBY_8") (pintype "bidirectional"))
      (node (ref "U$2") (pin "5") (pinfunction "GND_5") (pintype "bidirectional"))
      (node (ref "U$26") (pin "2") (pinfunction "GND_2") (pintype "power_in"))
      (node (ref "U$27") (pin "P$6") (pinfunction "6_P$6") (pintype "passive"))
      (node (ref "U$27") (pin "P$7") (pinfunction "7_P$7") (pintype "passive"))
      (node (ref "U$27") (pin "P$8") (pinfunction "8_P$8") (pintype "passive"))
      (node (ref "U$29") (pin "4") (pinfunction "GND_4") (pintype "bidirectional"))
      (node (ref "U$3") (pin "2") (pinfunction "VSS_2") (pintype "power_in"))
      (node (ref "U$3") (pin "8") (pinfunction "STBY_8") (pintype "bidirectional"))
      (node (ref "U$32") (pin "10") (pinfunction "GND_10") (pintype "bidirectional"))
      (node (ref "U$32") (pin "9") (pinfunction "AD0_9") (pintype "bidirectional"))
      (node (ref "U$4") (pin "P$6") (pinfunction "6_P$6") (pintype "passive"))
      (node (ref "U$4") (pin "P$7") (pinfunction "7_P$7") (pintype "passive"))
      (node (ref "U$4") (pin "P$8") (pinfunction "8_P$8") (pintype "passive"))
      (node (ref "U$5") (pin "P$6") (pinfunction "6_P$6") (pintype "passive"))
      (node (ref "U$5") (pin "P$7") (pinfunction "7_P$7") (pintype "passive"))
      (node (ref "U$5") (pin "P$8") (pinfunction "8_P$8") (pintype "passive"))
      (node (ref "U$58") (pin "7") (pinfunction "C_7") (pintype "bidirectional"))
      (node (ref "U$61") (pin "2") (pinfunction "GND_2") (pintype "power_in"))
      (node (ref "U$61") (pin "4") (pinfunction "GND_4") (pintype "power_in"))
      (node (ref "U$68") (pin "3") (pinfunction "G_3") (pintype "bidirectional"))
      (node (ref "U$75") (pin "4") (pinfunction "GND_4") (pintype "bidirectional"))
      (node (ref "U$8") (pin "K") (pinfunction "K_K") (pintype "bidirectional"))
      (node (ref "U$82") (pin "1") (pinfunction "1_1") (pintype "bidirectional"))
      (node (ref "U$82") (pin "4") (pinfunction "4_4") (pintype "bidirectional"))
      (node (ref "U$9") (pin "P$6") (pinfunction "6_P$6") (pintype "passive"))
      (node (ref "U$9") (pin "P$7") (pinfunction "7_P$7") (pintype "passive"))
      (node (ref "U$9") (pin "P$8") (pinfunction "8_P$8") (pintype "passive"))
      (node (ref "X1") (pin "12") (pinfunction "S_12") (pintype "passive"))
      (node (ref "X1") (pin "14") (pinfunction "S_14") (pintype "passive"))
      (node (ref "X1") (pin "2") (pinfunction "S_2") (pintype "passive"))
      (node (ref "X2") (pin "2") (pinfunction "S_2") (pintype "passive"))
      (node (ref "X3") (pin "2") (pinfunction "S_2") (pintype "passive"))
      (node (ref "X4") (pin "2") (pinfunction "2_2") (pintype "bidirectional"))
      (node (ref "X5") (pin "2") (pinfunction "2_2") (pintype "bidirectional"))
    )
    (net (code "90") (name "Net-(D2-PadC)") (class "Default")
      (node (ref "D2") (pin "C") (pinfunction "C_C") (pintype "passive"))
      (node (ref "X5") (pin "3") (pinfunction "3_3") (pintype "bidirectional"))
    )
    (net (code "91") (name "Net-(D3-PadC)") (class "Default")
      (node (ref "D3") (pin "C") (pinfunction "C_C") (pintype "passive"))
      (node (ref "X5") (pin "4") (pinfunction "4_4") (pintype "bidirectional"))
    )
    (net (code "92") (name "Net-(D4-PadC)") (class "Default")
      (node (ref "D4") (pin "C") (pinfunction "C_C") (pintype "passive"))
      (node (ref "X4") (pin "3") (pinfunction "3_3") (pintype "bidirectional"))
    )
    (net (code "93") (name "Net-(D5-PadC)") (class "Default")
      (node (ref "D5") (pin "C") (pinfunction "C_C") (pintype "passive"))
      (node (ref "X4") (pin "4") (pinfunction "4_4") (pintype "bidirectional"))
    )
    (net (code "94") (name "Net-(IC1-~{RES})") (class "Default")
      (node (ref "IC1") (pin "2") (pinfunction "~{RES}_2") (pintype "output"))
      (node (ref "R15") (pin "2") (pinfunction "2_2") (pintype "passive"))
    )
    (net (code "95") (name "Net-(IC4-3V3OUT)") (class "Default")
      (node (ref "C9") (pin "2") (pinfunction "2_2") (pintype "passive"))
      (node (ref "IC4") (pin "17") (pinfunction "3V3OUT_17") (pintype "output"))
      (node (ref "IC4") (pin "4") (pinfunction "VCCIO_4") (pintype "power_in"))
    )
    (net (code "96") (name "Net-(IC4-USBDM)") (class "Default")
      (node (ref "IC4") (pin "16") (pinfunction "USBDM_16") (pintype "bidirectional"))
      (node (ref "U$2") (pin "2") (pinfunction "D-_2") (pintype "bidirectional"))
    )
    (net (code "97") (name "Net-(IC4-USBDP)") (class "Default")
      (node (ref "IC4") (pin "15") (pinfunction "USBDP_15") (pintype "bidirectional"))
      (node (ref "U$2") (pin "3") (pinfunction "D+_3") (pintype "bidirectional"))
    )
    (net (code "98") (name "Net-(IC6-RB14)") (class "Default")
      (node (ref "IC6") (pin "14") (pinfunction "RB14_14") (pintype "bidirectional"))
      (node (ref "LED9") (pin "A") (pinfunction "A_A") (pintype "passive"))
    )
    (net (code "99") (name "Net-(IC6-RB15)") (class "Default")
      (node (ref "IC6") (pin "15") (pinfunction "RB15_15") (pintype "bidirectional"))
      (node (ref "LED8") (pin "A") (pinfunction "A_A") (pintype "passive"))
    )
    (net (code "100") (name "Net-(IC6-VDDCORE)") (class "Default")
      (node (ref "C40") (pin "2") (pinfunction "2_2") (pintype "passive"))
      (node (ref "IC6") (pin "7") (pinfunction "VDDCORE_7") (pintype "power_in"))
    )
    (net (code "101") (name "Net-(JP1-Pad1)") (class "Default")
      (node (ref "JP1") (pin "1") (pinfunction "1_1") (pintype "passive"))
      (node (ref "R4") (pin "2") (pinfunction "2_2") (pintype "passive"))
    )
    (net (code "102") (name "Net-(JP2-Pad1)") (class "Default")
      (node (ref "JP2") (pin "1") (pinfunction "1_1") (pintype "passive"))
      (node (ref "R3") (pin "2") (pinfunction "2_2") (pintype "passive"))
    )
    (net (code "103") (name "Net-(LED1-PadA)") (class "Default")
      (node (ref "LED1") (pin "A") (pinfunction "A_A") (pintype "passive"))
      (node (ref "R5") (pin "1") (pinfunction "1_1") (pintype "passive"))
    )
    (net (code "104") (name "Net-(LED2-PadA)") (class "Default")
      (node (ref "LED2") (pin "A") (pinfunction "A_A") (pintype "passive"))
      (node (ref "R6") (pin "1") (pinfunction "1_1") (pintype "passive"))
    )
    (net (code "105") (name "Net-(LED3-PadA)") (class "Default")
      (node (ref "LED3") (pin "A") (pinfunction "A_A") (pintype "passive"))
      (node (ref "R7") (pin "1") (pinfunction "1_1") (pintype "passive"))
    )
    (net (code "106") (name "Net-(LED4-PadA)") (class "Default")
      (node (ref "LED4") (pin "A") (pinfunction "A_A") (pintype "passive"))
      (node (ref "R12") (pin "1") (pinfunction "1_1") (pintype "passive"))
    )
    (net (code "107") (name "Net-(LED5-PadA)") (class "Default")
      (node (ref "LED5") (pin "A") (pinfunction "A_A") (pintype "passive"))
      (node (ref "R_MD3") (pin "1") (pinfunction "1_1") (pintype "passive"))
    )
    (net (code "108") (name "Net-(LED8-PadC)") (class "Default")
      (node (ref "LED8") (pin "C") (pinfunction "C_C") (pintype "passive"))
      (node (ref "R57") (pin "1") (pinfunction "1_1") (pintype "passive"))
    )
    (net (code "109") (name "Net-(LED9-PadC)") (class "Default")
      (node (ref "LED9") (pin "C") (pinfunction "C_C") (pintype "passive"))
      (node (ref "R58") (pin "1") (pinfunction "1_1") (pintype "passive"))
    )
    (net (code "110") (name "Net-(Q1-D)") (class "Default")
      (node (ref "Q1") (pin "3") (pinfunction "D_3") (pintype "bidirectional"))
      (node (ref "R45") (pin "1") (pinfunction "1_1") (pintype "passive"))
    )
    (net (code "111") (name "Net-(Q2-D)") (class "Default")
      (node (ref "Q2") (pin "3") (pinfunction "D_3") (pintype "bidirectional"))
      (node (ref "R46") (pin "1") (pinfunction "1_1") (pintype "passive"))
    )
    (net (code "112") (name "Net-(Q3-D)") (class "Default")
      (node (ref "Q3") (pin "3") (pinfunction "D_3") (pintype "bidirectional"))
      (node (ref "R47") (pin "1") (pinfunction "1_1") (pintype "passive"))
    )
    (net (code "113") (name "Net-(Q4-D)") (class "Default")
      (node (ref "Q4") (pin "3") (pinfunction "D_3") (pintype "bidirectional"))
      (node (ref "SG2") (pin "2") (pinfunction "2_2") (pintype "passive"))
    )
    (net (code "114") (name "Net-(R22-Pad2)") (class "Default")
      (node (ref "R22") (pin "2") (pinfunction "2_2") (pintype "passive"))
      (node (ref "U$7") (pin "3") (pinfunction "3_3") (pintype "bidirectional"))
      (node (ref "U$7") (pin "6") (pinfunction "6_6") (pintype "bidirectional"))
    )
    (net (code "115") (name "Net-(R28-Pad2)") (class "Default")
      (node (ref "R28") (pin "2") (pinfunction "2_2") (pintype "passive"))
      (node (ref "U$7") (pin "1") (pinfunction "1_1") (pintype "bidirectional"))
      (node (ref "U$7") (pin "4") (pinfunction "4_4") (pintype "bidirectional"))
    )
    (net (code "116") (name "Net-(R40-Pad1)") (class "Default")
      (node (ref "R40") (pin "1") (pinfunction "1_1") (pintype "passive"))
      (node (ref "U$11") (pin "TRIM") (pinfunction "TRIM_TRIM") (pintype "bidirectional"))
    )
    (net (code "117") (name "Net-(R41-Pad2)") (class "Default")
      (node (ref "R41") (pin "2") (pinfunction "2_2") (pintype "passive"))
      (node (ref "U$8") (pin "A") (pinfunction "A_A") (pintype "bidirectional"))
    )
    (net (code "118") (name "Net-(R_MD4-Pad2)") (class "Default")
      (node (ref "R_MD4") (pin "2") (pinfunction "2_2") (pintype "passive"))
      (node (ref "U$82") (pin "3") (pinfunction "3_3") (pintype "bidirectional"))
      (node (ref "U$82") (pin "6") (pinfunction "6_6") (pintype "bidirectional"))
    )
    (net (code "119") (name "Net-(U$1-P35{slash}NMI)") (class "Default")
      (node (ref "R_NMI") (pin "2") (pinfunction "2_2") (pintype "passive"))
      (node (ref "U$1") (pin "15") (pinfunction "P35/NMI_15") (pintype "bidirectional"))
    )
    (net (code "120") (name "Net-(U$1-PD6{slash}AN6)") (class "Default")
      (node (ref "R7") (pin "2") (pinfunction "2_2") (pintype "passive"))
      (node (ref "U$1") (pin "80") (pinfunction "PD6/AN6_80") (pintype "bidirectional"))
    )
    (net (code "121") (name "Net-(U$1-PD7{slash}AN7)") (class "Default")
      (node (ref "R12") (pin "2") (pinfunction "2_2") (pintype "passive"))
      (node (ref "U$1") (pin "79") (pinfunction "PD7/AN7_79") (pintype "bidirectional"))
    )
    (net (code "122") (name "Net-(U$1-PE0{slash}SCK12{slash}ANEX0)") (class "Default")
      (node (ref "R6") (pin "2") (pinfunction "2_2") (pintype "passive"))
      (node (ref "U$1") (pin "78") (pinfunction "PE0/SCK12/ANEX0_78") (pintype "bidirectional"))
    )
    (net (code "123") (name "Net-(U$1-PE1{slash}MTIOC4C{slash}TXD12{slash}ANEX1)") (class "Default")
      (node (ref "R5") (pin "2") (pinfunction "2_2") (pintype "passive"))
      (node (ref "U$1") (pin "77") (pinfunction "PE1/MTIOC4C/TXD12/ANEX1_77") (pintype "bidirectional"))
    )
    (net (code "124") (name "Net-(U$1-VCL)") (class "Default")
      (node (ref "C1") (pin "1") (pinfunction "1_1") (pintype "passive"))
      (node (ref "U$1") (pin "5") (pinfunction "VCL_5") (pintype "bidirectional"))
    )
    (net (code "125") (name "Net-(U$1-XCIN)") (class "Default")
      (node (ref "R_XCIN") (pin "2") (pinfunction "2_2") (pintype "passive"))
      (node (ref "U$1") (pin "8") (pinfunction "XCIN_8") (pintype "bidirectional"))
    )
    (net (code "126") (name "Net-(U$3-CANH)") (class "Default")
      (node (ref "JP1") (pin "2") (pinfunction "2_2") (pintype "passive"))
      (node (ref "U$3") (pin "7") (pinfunction "CANH_7") (pintype "bidirectional"))
      (node (ref "U$4") (pin "P$5") (pinfunction "5_P$5") (pintype "passive"))
      (node (ref "U$5") (pin "P$5") (pinfunction "5_P$5") (pintype "passive"))
    )
    (net (code "127") (name "Net-(U$3-CANL)") (class "Default")
      (node (ref "R4") (pin "1") (pinfunction "1_1") (pintype "passive"))
      (node (ref "U$3") (pin "6") (pinfunction "CANL_6") (pintype "bidirectional"))
      (node (ref "U$4") (pin "P$4") (pinfunction "4_P$4") (pintype "passive"))
      (node (ref "U$5") (pin "P$4") (pinfunction "4_P$4") (pintype "passive"))
    )
    (net (code "128") (name "Net-(U$17-CANH)") (class "Default")
      (node (ref "JP2") (pin "2") (pinfunction "2_2") (pintype "passive"))
      (node (ref "U$17") (pin "7") (pinfunction "CANH_7") (pintype "bidirectional"))
      (node (ref "U$27") (pin "P$5") (pinfunction "5_P$5") (pintype "passive"))
      (node (ref "U$9") (pin "P$5") (pinfunction "5_P$5") (pintype "passive"))
    )
    (net (code "129") (name "Net-(U$17-CANL)") (class "Default")
      (node (ref "R3") (pin "1") (pinfunction "1_1") (pintype "passive"))
      (node (ref "U$17") (pin "6") (pinfunction "CANL_6") (pintype "bidirectional"))
      (node (ref "U$27") (pin "P$4") (pinfunction "4_P$4") (pintype "passive"))
      (node (ref "U$9") (pin "P$4") (pinfunction "4_P$4") (pintype "passive"))
    )
    (net (code "130") (name "Net-(U$58-BLUE)") (class "Default")
      (node (ref "R47") (pin "2") (pinfunction "2_2") (pintype "passive"))
      (node (ref "U$58") (pin "4") (pinfunction "BLUE_4") (pintype "bidirectional"))
    )
    (net (code "131") (name "Net-(U$58-GREEN)") (class "Default")
      (node (ref "R46") (pin "2") (pinfunction "2_2") (pintype "passive"))
      (node (ref "U$58") (pin "2") (pinfunction "GREEN_2") (pintype "bidirectional"))
    )
    (net (code "132") (name "Net-(U$58-RED)") (class "Default")
      (node (ref "R45") (pin "2") (pinfunction "2_2") (pintype "passive"))
      (node (ref "U$58") (pin "1") (pinfunction "RED_1") (pintype "bidirectional"))
    )
    (net (code "133") (name "Net-(U$68A-I)") (class "Default")
      (node (ref "U$68") (pin "2") (pinfunction "I_2") (pintype "input"))
      (node (ref "U$82") (pin "2") (pinfunction "2_2") (pintype "bidirectional"))
      (node (ref "U$82") (pin "5") (pinfunction "5_5") (pintype "bidirectional"))
    )
    (net (code "134") (name "Net-(U$75-VBUS)") (class "Default")
      (node (ref "U$75") (pin "1") (pinfunction "VBUS_1") (pintype "bidirectional"))
      (node (ref "U$76") (pin "1") (pinfunction "1_1") (pintype "passive"))
    )
    (net (code "135") (name "Net-(X2B-S)") (class "Default")
      (node (ref "U$40") (pin "1") (pinfunction "1_1") (pintype "passive"))
      (node (ref "X2") (pin "10") (pinfunction "S_10") (pintype "passive"))
    )
    (net (code "136") (name "Net-(X2C-S)") (class "Default")
      (node (ref "U$41") (pin "1") (pinfunction "1_1") (pintype "passive"))
      (node (ref "X2") (pin "11") (pinfunction "S_11") (pintype "passive"))
    )
    (net (code "137") (name "Net-(X2D-S)") (class "Default")
      (node (ref "U$42") (pin "1") (pinfunction "1_1") (pintype "passive"))
      (node (ref "X2") (pin "12") (pinfunction "S_12") (pintype "passive"))
    )
    (net (code "138") (name "Net-(X2E-S)") (class "Default")
      (node (ref "U$43") (pin "1") (pinfunction "1_1") (pintype "passive"))
      (node (ref "X2") (pin "13") (pinfunction "S_13") (pintype "passive"))
    )
    (net (code "139") (name "Net-(X2F-S)") (class "Default")
      (node (ref "U$44") (pin "1") (pinfunction "1_1") (pintype "passive"))
      (node (ref "X2") (pin "14") (pinfunction "S_14") (pintype "passive"))
    )
    (net (code "140") (name "Net-(X2G-S)") (class "Default")
      (node (ref "U$45") (pin "1") (pinfunction "1_1") (pintype "passive"))
      (node (ref "X2") (pin "15") (pinfunction "S_15") (pintype "passive"))
    )
    (net (code "141") (name "Net-(X2H-S)") (class "Default")
      (node (ref "U$46") (pin "1") (pinfunction "1_1") (pintype "passive"))
      (node (ref "X2") (pin "16") (pinfunction "S_16") (pintype "passive"))
    )
    (net (code "142") (name "Net-(X2J-S)") (class "Default")
      (node (ref "U$33") (pin "1") (pinfunction "1_1") (pintype "passive"))
      (node (ref "X2") (pin "3") (pinfunction "S_3") (pintype "passive"))
    )
    (net (code "143") (name "Net-(X2K-S)") (class "Default")
      (node (ref "U$34") (pin "1") (pinfunction "1_1") (pintype "passive"))
      (node (ref "X2") (pin "4") (pinfunction "S_4") (pintype "passive"))
    )
    (net (code "144") (name "Net-(X2L-S)") (class "Default")
      (node (ref "U$35") (pin "1") (pinfunction "1_1") (pintype "passive"))
      (node (ref "X2") (pin "5") (pinfunction "S_5") (pintype "passive"))
    )
    (net (code "145") (name "Net-(X2M-S)") (class "Default")
      (node (ref "U$36") (pin "1") (pinfunction "1_1") (pintype "passive"))
      (node (ref "X2") (pin "6") (pinfunction "S_6") (pintype "passive"))
    )
    (net (code "146") (name "Net-(X2N-S)") (class "Default")
      (node (ref "U$37") (pin "1") (pinfunction "1_1") (pintype "passive"))
      (node (ref "X2") (pin "7") (pinfunction "S_7") (pintype "passive"))
    )
    (net (code "147") (name "Net-(X2O-S)") (class "Default")
      (node (ref "U$38") (pin "1") (pinfunction "1_1") (pintype "passive"))
      (node (ref "X2") (pin "8") (pinfunction "S_8") (pintype "passive"))
    )
    (net (code "148") (name "Net-(X2P-S)") (class "Default")
      (node (ref "U$39") (pin "1") (pinfunction "1_1") (pintype "passive"))
      (node (ref "X2") (pin "9") (pinfunction "S_9") (pintype "passive"))
    )
    (net (code "149") (name "VCC") (class "Default")
      (node (ref "C10") (pin "2") (pinfunction "2_2") (pintype "passive"))
      (node (ref "C11") (pin "2") (pinfunction "2_2") (pintype "passive"))
      (node (ref "C3") (pin "1") (pinfunction "1_1") (pintype "passive"))
      (node (ref "C34") (pin "2") (pinfunction "2_2") (pintype "passive"))
      (node (ref "C6") (pin "2") (pinfunction "2_2") (pintype "passive"))
      (node (ref "C7") (pin "2") (pinfunction "2_2") (pintype "passive"))
      (node (ref "D1") (pin "A") (pinfunction "A_A") (pintype "passive"))
      (node (ref "IC4") (pin "20") (pinfunction "VCC_20") (pintype "power_in"))
      (node (ref "IC6") (pin "42") (pinfunction "RB6_42") (pintype "bidirectional"))
      (node (ref "R41") (pin "1") (pinfunction "1_1") (pintype "passive"))
      (node (ref "SG2") (pin "1") (pinfunction "1_1") (pintype "passive"))
      (node (ref "U$11") (pin "SENSE") (pinfunction "SENSE_SENSE") (pintype "bidirectional"))
      (node (ref "U$11") (pin "VOUT") (pinfunction "VOUT_VOUT") (pintype "bidirectional"))
      (node (ref "U$17") (pin "3") (pinfunction "VDD_3") (pintype "power_in"))
      (node (ref "U$26") (pin "1") (pinfunction "IN_1") (pintype "power_in"))
      (node (ref "U$27") (pin "P$1") (pinfunction "1_P$1") (pintype "passive"))
      (node (ref "U$27") (pin "P$2") (pinfunction "2_P$2") (pintype "passive"))
      (node (ref "U$27") (pin "P$3") (pinfunction "3_P$3") (pintype "passive"))
      (node (ref "U$29") (pin "1") (pinfunction "VBUS_1") (pintype "bidirectional"))
      (node (ref "U$3") (pin "3") (pinfunction "VDD_3") (pintype "power_in"))
      (node (ref "U$4") (pin "P$1") (pinfunction "1_P$1") (pintype "passive"))
      (node (ref "U$4") (pin "P$2") (pinfunction "2_P$2") (pintype "passive"))
      (node (ref "U$4") (pin "P$3") (pinfunction "3_P$3") (pintype "passive"))
      (node (ref "U$5") (pin "P$1") (pinfunction "1_P$1") (pintype "passive"))
      (node (ref "U$5") (pin "P$2") (pinfunction "2_P$2") (pintype "passive"))
      (node (ref "U$5") (pin "P$3") (pinfunction "3_P$3") (pintype "passive"))
      (node (ref "U$76") (pin "2") (pinfunction "2_2") (pintype "passive"))
      (node (ref "U$9") (pin "P$1") (pinfunction "1_P$1") (pintype "passive"))
      (node (ref "U$9") (pin "P$2") (pinfunction "2_P$2") (pintype "passive"))
      (node (ref "U$9") (pin "P$3") (pinfunction "3_P$3") (pintype "passive"))
      (node (ref "X4") (pin "1") (pinfunction "1_1") (pintype "bidirectional"))
      (node (ref "X5") (pin "1") (pinfunction "1_1") (pintype "bidirectional"))
    )
    (net (code "150") (name "unconnected-(IC4-CBUS0-Pad23)") (class "Default")
      (node (ref "IC4") (pin "23") (pinfunction "CBUS0_23") (pintype "bidirectional"))
    )
    (net (code "151") (name "unconnected-(IC4-CBUS1-Pad22)") (class "Default")
      (node (ref "IC4") (pin "22") (pinfunction "CBUS1_22") (pintype "bidirectional"))
    )
    (net (code "152") (name "unconnected-(IC4-CBUS2-Pad13)") (class "Default")
      (node (ref "IC4") (pin "13") (pinfunction "CBUS2_13") (pintype "bidirectional"))
    )
    (net (code "153") (name "unconnected-(IC4-CBUS3-Pad14)") (class "Default")
      (node (ref "IC4") (pin "14") (pinfunction "CBUS3_14") (pintype "bidirectional"))
    )
    (net (code "154") (name "unconnected-(IC4-CBUS4-Pad12)") (class "Default")
      (node (ref "IC4") (pin "12") (pinfunction "CBUS4_12") (pintype "bidirectional"))
    )
    (net (code "155") (name "unconnected-(IC4-OSCI-Pad27)") (class "Default")
      (node (ref "IC4") (pin "27") (pinfunction "OSCI_27") (pintype "input"))
    )
    (net (code "156") (name "unconnected-(IC4-OSCO-Pad28)") (class "Default")
      (node (ref "IC4") (pin "28") (pinfunction "OSCO_28") (pintype "output"))
    )
    (net (code "157") (name "unconnected-(IC4-~{CTS}-Pad11)") (class "Default")
      (node (ref "IC4") (pin "11") (pinfunction "~{CTS}_11") (pintype "input"))
    )
    (net (code "158") (name "unconnected-(IC4-~{DCD}-Pad10)") (class "Default")
      (node (ref "IC4") (pin "10") (pinfunction "~{DCD}_10") (pintype "input"))
    )
    (net (code "159") (name "unconnected-(IC4-~{DSR}-Pad9)") (class "Default")
      (node (ref "IC4") (pin "9") (pinfunction "~{DSR}_9") (pintype "input"))
    )
    (net (code "160") (name "unconnected-(IC4-~{DTR}-Pad2)") (class "Default")
      (node (ref "IC4") (pin "2") (pinfunction "~{DTR}_2") (pintype "output"))
    )
    (net (code "161") (name "unconnected-(IC4-~{RESET}-Pad19)") (class "Default")
      (node (ref "IC4") (pin "19") (pinfunction "~{RESET}_19") (pintype "input"))
    )
    (net (code "162") (name "unconnected-(IC4-~{RI}-Pad6)") (class "Default")
      (node (ref "IC4") (pin "6") (pinfunction "~{RI}_6") (pintype "input"))
    )
    (net (code "163") (name "unconnected-(IC4-~{RTS}-Pad3)") (class "Default")
      (node (ref "IC4") (pin "3") (pinfunction "~{RTS}_3") (pintype "output"))
    )
    (net (code "164") (name "unconnected-(IC6-RA0-Pad19)") (class "Default")
      (node (ref "IC6") (pin "19") (pinfunction "RA0_19") (pintype "bidirectional"))
    )
    (net (code "165") (name "unconnected-(IC6-RA1-Pad20)") (class "Default")
      (node (ref "IC6") (pin "20") (pinfunction "RA1_20") (pintype "bidirectional"))
    )
    (net (code "166") (name "unconnected-(IC6-RA2-Pad30)") (class "Default")
      (node (ref "IC6") (pin "30") (pinfunction "RA2_30") (pintype "bidirectional"))
    )
    (net (code "167") (name "unconnected-(IC6-RA3-Pad31)") (class "Default")
      (node (ref "IC6") (pin "31") (pinfunction "RA3_31") (pintype "bidirectional"))
    )
    (net (code "168") (name "unconnected-(IC6-RA4-Pad34)") (class "Default")
      (node (ref "IC6") (pin "34") (pinfunction "RA4_34") (pintype "bidirectional"))
    )
    (net (code "169") (name "unconnected-(IC6-RB2-Pad23)") (class "Default")
      (node (ref "IC6") (pin "23") (pinfunction "RB2_23") (pintype "bidirectional"))
    )
    (net (code "170") (name "unconnected-(IC6-RB3-Pad24)") (class "Default")
      (node (ref "IC6") (pin "24") (pinfunction "RB3_24") (pintype "bidirectional"))
    )
    (net (code "171") (name "unconnected-(IC6-RB4-Pad33)") (class "Default")
      (node (ref "IC6") (pin "33") (pinfunction "RB4_33") (pintype "bidirectional"))
    )
    (net (code "172") (name "unconnected-(IC6-RB5-Pad41)") (class "Default")
      (node (ref "IC6") (pin "41") (pinfunction "RB5_41") (pintype "bidirectional"))
    )
    (net (code "173") (name "unconnected-(IC6-RB7-Pad43)") (class "Default")
      (node (ref "IC6") (pin "43") (pinfunction "RB7_43") (pintype "bidirectional"))
    )
    (net (code "174") (name "unconnected-(IC6-RB8-Pad44)") (class "Default")
      (node (ref "IC6") (pin "44") (pinfunction "RB8_44") (pintype "bidirectional"))
    )
    (net (code "175") (name "unconnected-(IC6-RB13-Pad11)") (class "Default")
      (node (ref "IC6") (pin "11") (pinfunction "RB13_11") (pintype "bidirectional"))
    )
    (net (code "176") (name "unconnected-(IC6-RC0-Pad25)") (class "Default")
      (node (ref "IC6") (pin "25") (pinfunction "RC0_25") (pintype "bidirectional"))
    )
    (net (code "177") (name "unconnected-(IC6-RC1-Pad26)") (class "Default")
      (node (ref "IC6") (pin "26") (pinfunction "RC1_26") (pintype "bidirectional"))
    )
    (net (code "178") (name "unconnected-(IC6-RC2-Pad27)") (class "Default")
      (node (ref "IC6") (pin "27") (pinfunction "RC2_27") (pintype "bidirectional"))
    )
    (net (code "179") (name "unconnected-(IC6-RC3-Pad36)") (class "Default")
      (node (ref "IC6") (pin "36") (pinfunction "RC3_36") (pintype "bidirectional"))
    )
    (net (code "180") (name "unconnected-(IC6-RC4-Pad37)") (class "Default")
      (node (ref "IC6") (pin "37") (pinfunction "RC4_37") (pintype "bidirectional"))
    )
    (net (code "181") (name "unconnected-(IC6-RC5-Pad38)") (class "Default")
      (node (ref "IC6") (pin "38") (pinfunction "RC5_38") (pintype "bidirectional"))
    )
    (net (code "182") (name "unconnected-(IC6-TCK-Pad13)") (class "Default")
      (node (ref "IC6") (pin "13") (pinfunction "TCK_13") (pintype "input"))
    )
    (net (code "183") (name "unconnected-(IC6-TDI-Pad35)") (class "Default")
      (node (ref "IC6") (pin "35") (pinfunction "TDI_35") (pintype "input"))
    )
    (net (code "184") (name "unconnected-(IC6-TDO-Pad32)") (class "Default")
      (node (ref "IC6") (pin "32") (pinfunction "TDO_32") (pintype "output"))
    )
    (net (code "185") (name "unconnected-(IC6-TMS-Pad12)") (class "Default")
      (node (ref "IC6") (pin "12") (pinfunction "TMS_12") (pintype "input"))
    )
    (net (code "186") (name "unconnected-(S6-S-Pad3)") (class "Default")
      (node (ref "S6") (pin "3") (pinfunction "S_3") (pintype "passive"))
    )
    (net (code "187") (name "unconnected-(U$1-P05{slash}DA1-Pad100)") (class "Default")
      (node (ref "U$1") (pin "100") (pinfunction "P05/DA1_100") (pintype "bidirectional"))
    )
    (net (code "188") (name "unconnected-(U$1-P07-Pad98)") (class "Default")
      (node (ref "U$1") (pin "98") (pinfunction "P07_98") (pintype "bidirectional"))
    )
    (net (code "189") (name "unconnected-(U$1-P17{slash}MTIOC3A{slash}MTIOC3B{slash}SCK1{slash}TXD3-Pad29)") (class "Default")
      (node (ref "U$1") (pin "29") (pinfunction "P17/MTIOC3A/MTIOC3B/SCK1/TXD3_29") (pintype "bidirectional"))
    )
    (net (code "190") (name "unconnected-(U$1-P51{slash}SCK2-Pad43)") (class "Default")
      (node (ref "U$1") (pin "43") (pinfunction "P51/SCK2_43") (pintype "bidirectional"))
    )
    (net (code "191") (name "unconnected-(U$1-P53{slash}BCLK-Pad41)") (class "Default")
      (node (ref "U$1") (pin "41") (pinfunction "P53/BCLK_41") (pintype "bidirectional"))
    )
    (net (code "192") (name "unconnected-(U$1-PB0{slash}RXD6-Pad61)") (class "Default")
      (node (ref "U$1") (pin "61") (pinfunction "PB0/RXD6_61") (pintype "bidirectional"))
    )
    (net (code "193") (name "unconnected-(U$1-PB6{slash}MTIOC3D{slash}RXD9-Pad54)") (class "Default")
      (node (ref "U$1") (pin "54") (pinfunction "PB6/MTIOC3D/RXD9_54") (pintype "bidirectional"))
    )
    (net (code "194") (name "unconnected-(U$1-PC2{slash}MTIOC4B{slash}TCLKA{slash}RXD5-Pad50)") (class "Default")
      (node (ref "U$1") (pin "50") (pinfunction "PC2/MTIOC4B/TCLKA/RXD5_50") (pintype "bidirectional"))
    )
    (net (code "195") (name "unconnected-(U$1-PC3{slash}MTIOC4D{slash}TCLKB{slash}TXD5-Pad49)") (class "Default")
      (node (ref "U$1") (pin "49") (pinfunction "PC3/MTIOC4D/TCLKB/TXD5_49") (pintype "bidirectional"))
    )
    (net (code "196") (name "unconnected-(U$1-PC6{slash}MTIOC3C{slash}MTCLKA{slash}RXD8-Pad46)") (class "Default")
      (node (ref "U$1") (pin "46") (pinfunction "PC6/MTIOC3C/MTCLKA/RXD8_46") (pintype "bidirectional"))
    )
    (net (code "197") (name "unconnected-(U$1-PE7{slash}AN5-Pad71)") (class "Default")
      (node (ref "U$1") (pin "71") (pinfunction "PE7/AN5_71") (pintype "bidirectional"))
    )
    (net (code "198") (name "unconnected-(U$1-PJ3{slash}MITIOC3C-Pad4)") (class "Default")
      (node (ref "U$1") (pin "4") (pinfunction "PJ3/MITIOC3C_4") (pintype "bidirectional"))
    )
    (net (code "199") (name "unconnected-(U$1-XCOUT-Pad9)") (class "Default")
      (node (ref "U$1") (pin "9") (pinfunction "XCOUT_9") (pintype "bidirectional"))
    )
    (net (code "200") (name "unconnected-(U$2-ID(NC)-Pad4)") (class "Default")
      (node (ref "U$2") (pin "4") (pinfunction "ID(NC)_4") (pintype "bidirectional"))
    )
    (net (code "201") (name "unconnected-(U$11-PadPGOOD)") (class "Default")
      (node (ref "U$11") (pin "PGOOD") (pinfunction "PGOOD_PGOOD") (pintype "bidirectional"))
    )
    (net (code "202") (name "unconnected-(U$32-ES_CL-Pad6)") (class "Default")
      (node (ref "U$32") (pin "6") (pinfunction "ES_CL_6") (pintype "bidirectional"))
    )
    (net (code "203") (name "unconnected-(U$32-ES_DA-Pad5)") (class "Default")
      (node (ref "U$32") (pin "5") (pinfunction "ES_DA_5") (pintype "bidirectional"))
    )
    (net (code "204") (name "unconnected-(U$32-FSYNC-Pad7)") (class "Default")
      (node (ref "U$32") (pin "7") (pinfunction "FSYNC_7") (pintype "bidirectional"))
    )
    (net (code "205") (name "unconnected-(X1K-S-Pad6)") (class "Default")
      (node (ref "X1") (pin "6") (pinfunction "S_6") (pintype "passive"))
    )
  )
)
